# 03_-_28Pins_Schematic.net
KiCad netlist of a schematic drawn in Altium Designer
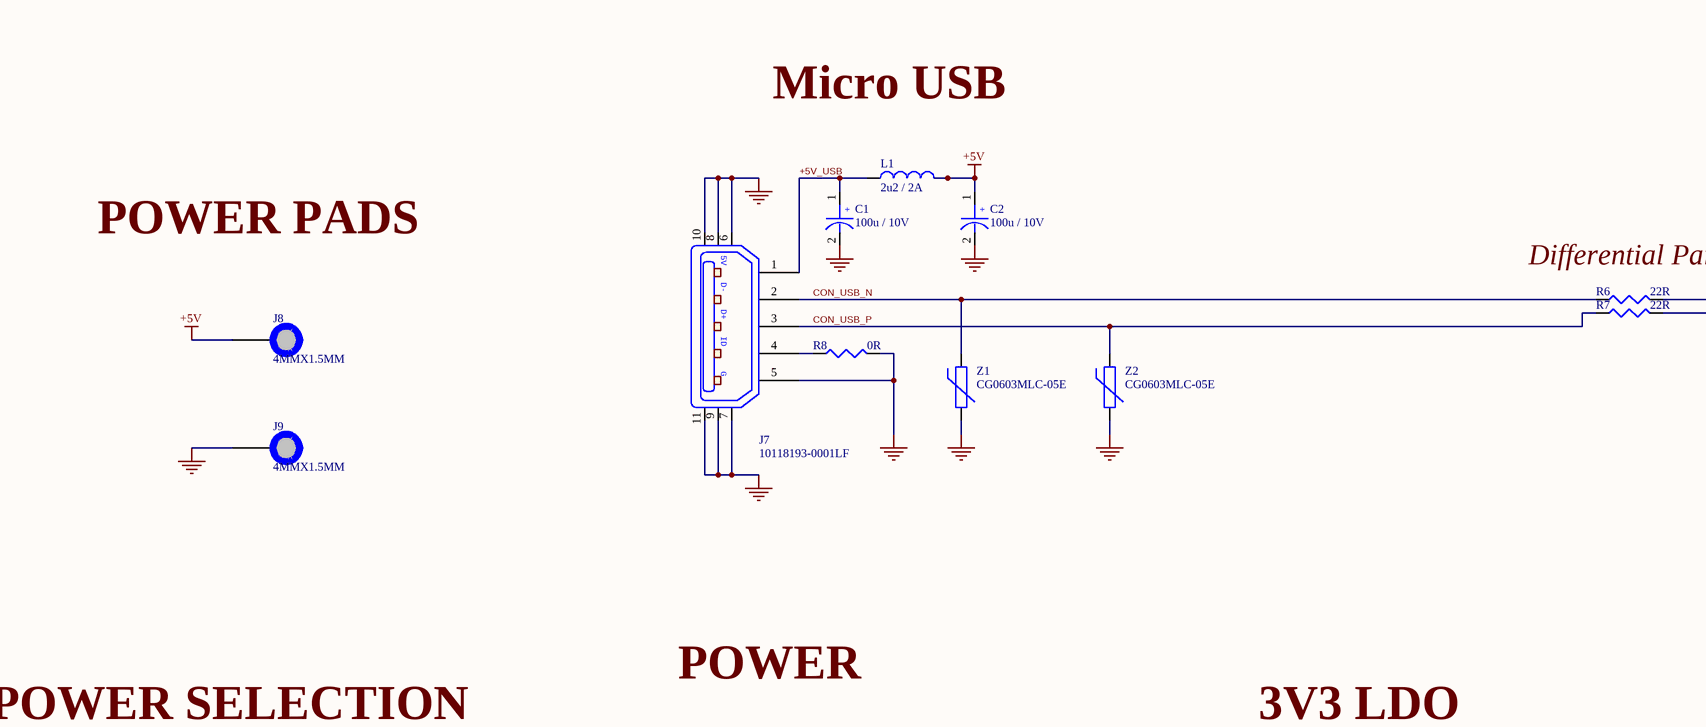
[diagram p0: [03] - 28Pins_Schematic.SchDoc, top left]
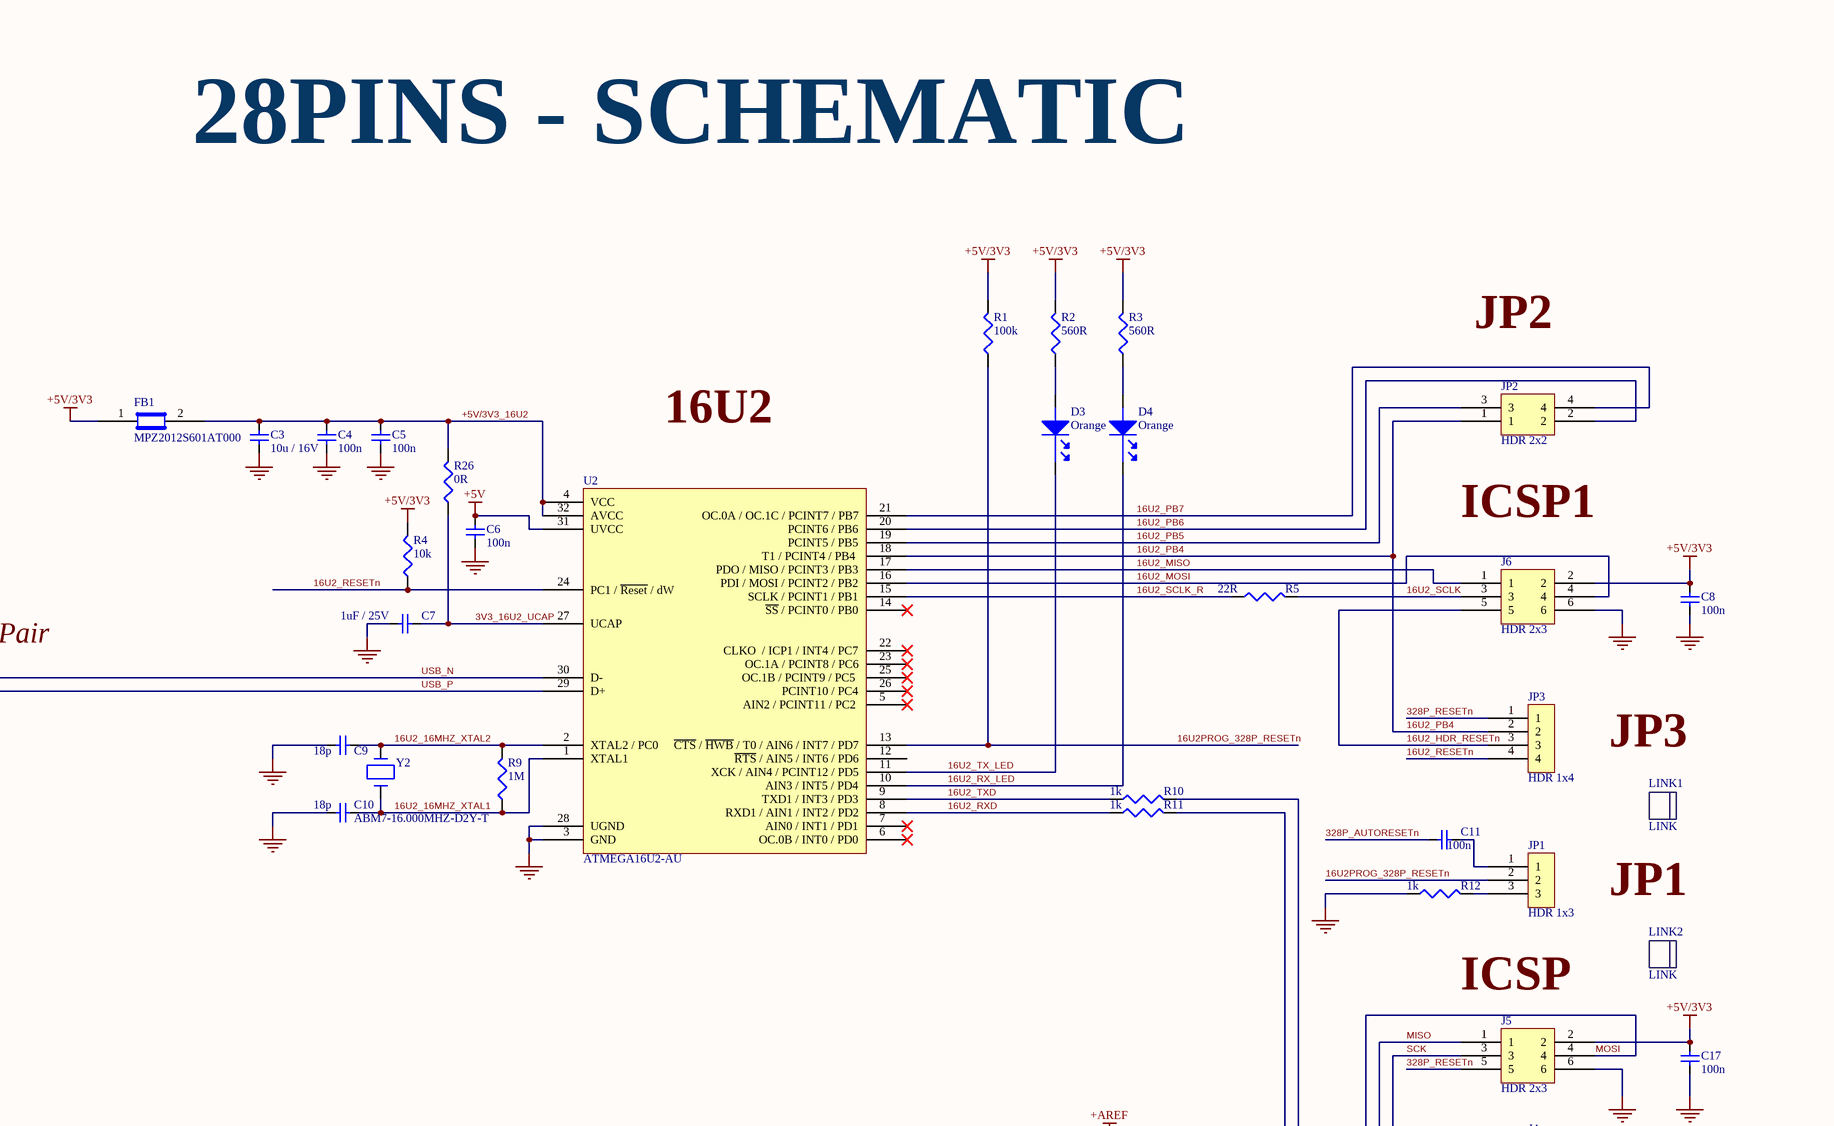
[diagram p1: [03] - 28Pins_Schematic.SchDoc, top middle]
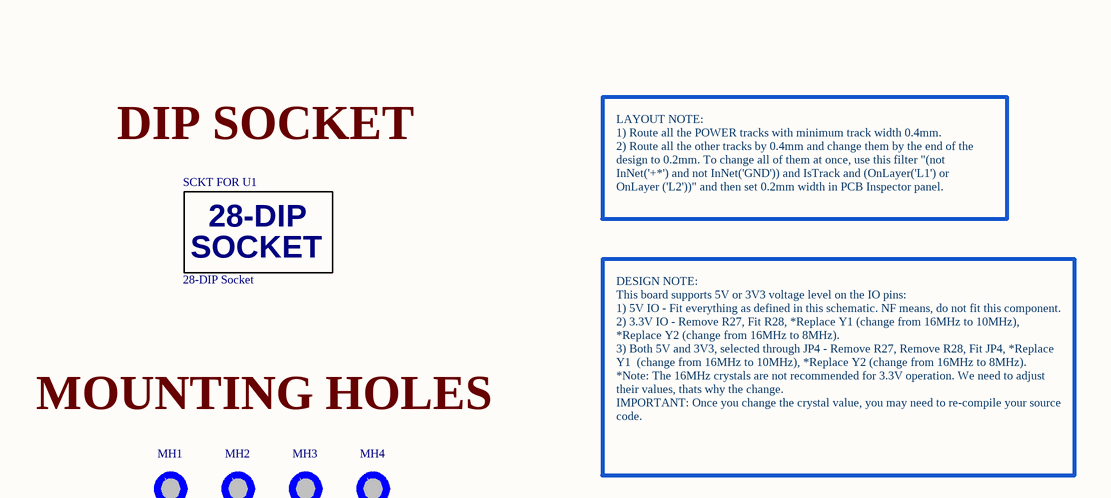
[diagram p2: [03] - 28Pins_Schematic.SchDoc, top right]
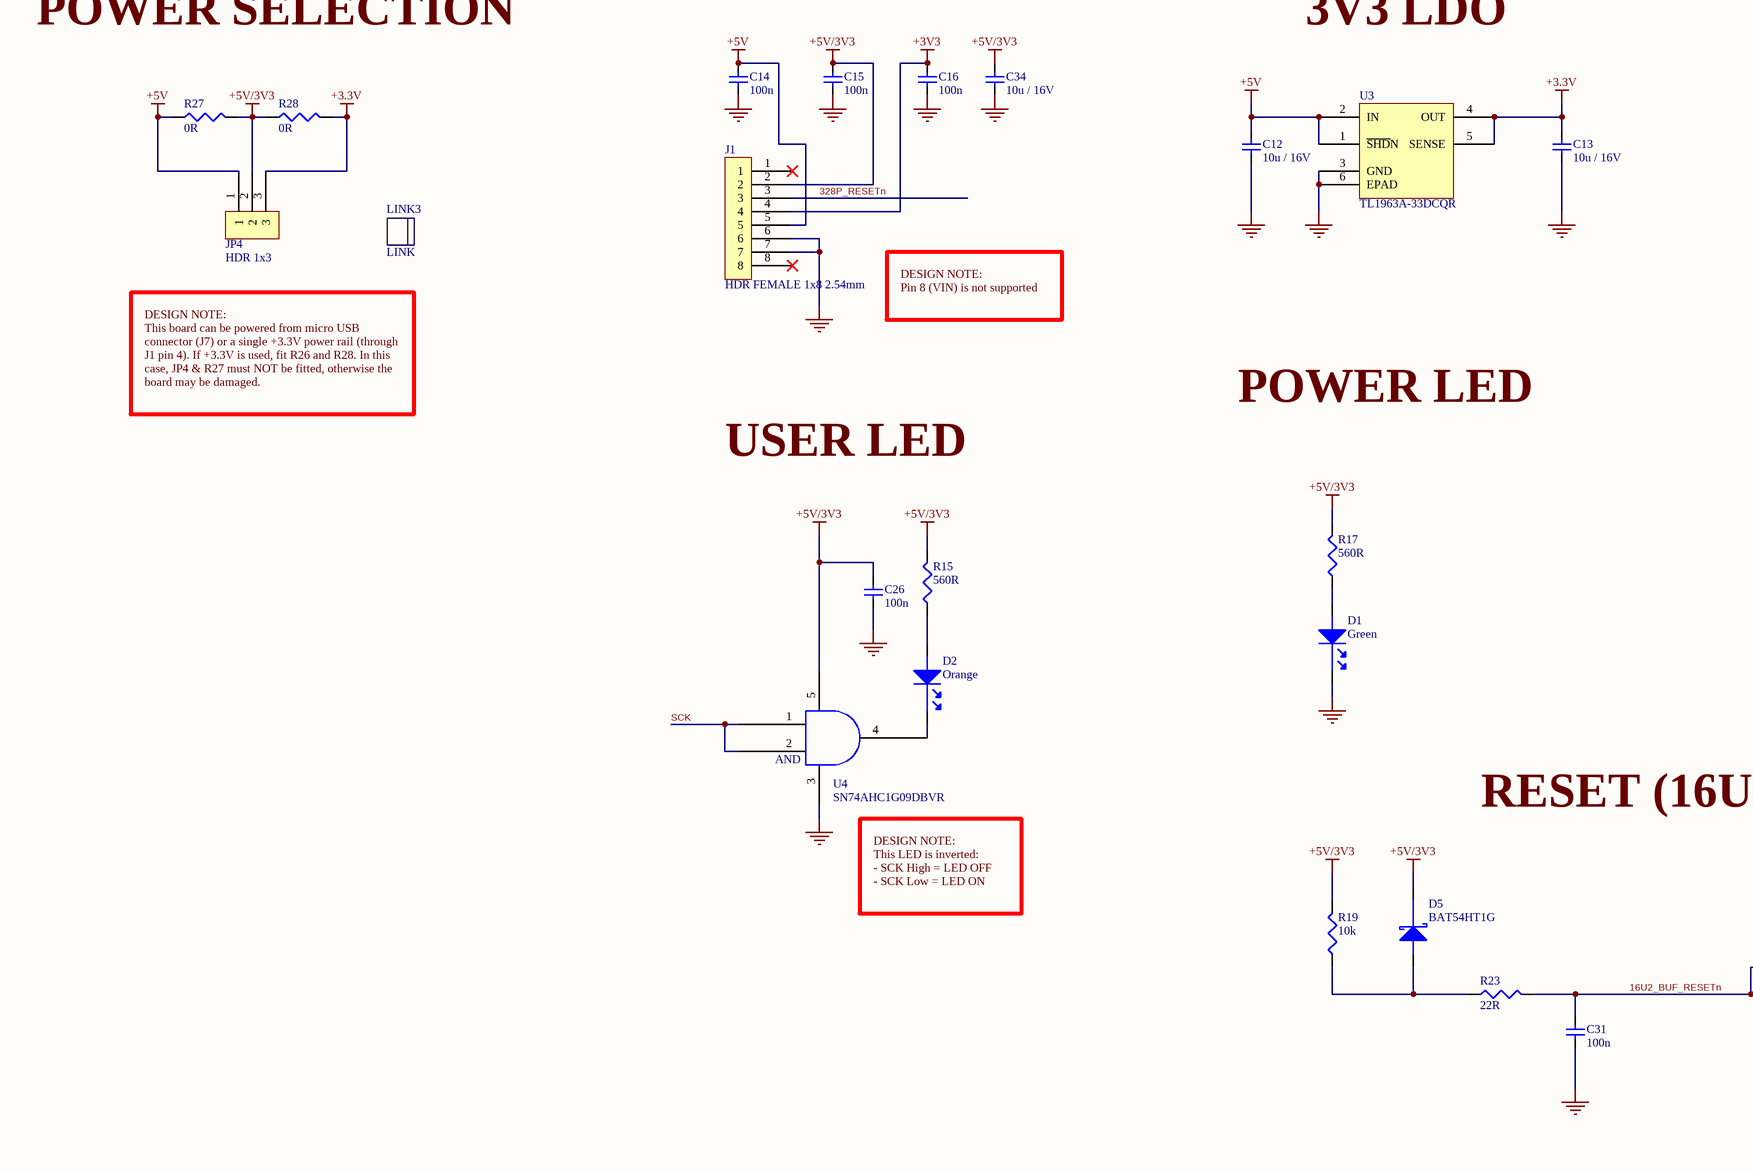
[diagram p3: [03] - 28Pins_Schematic.SchDoc, bottom left]
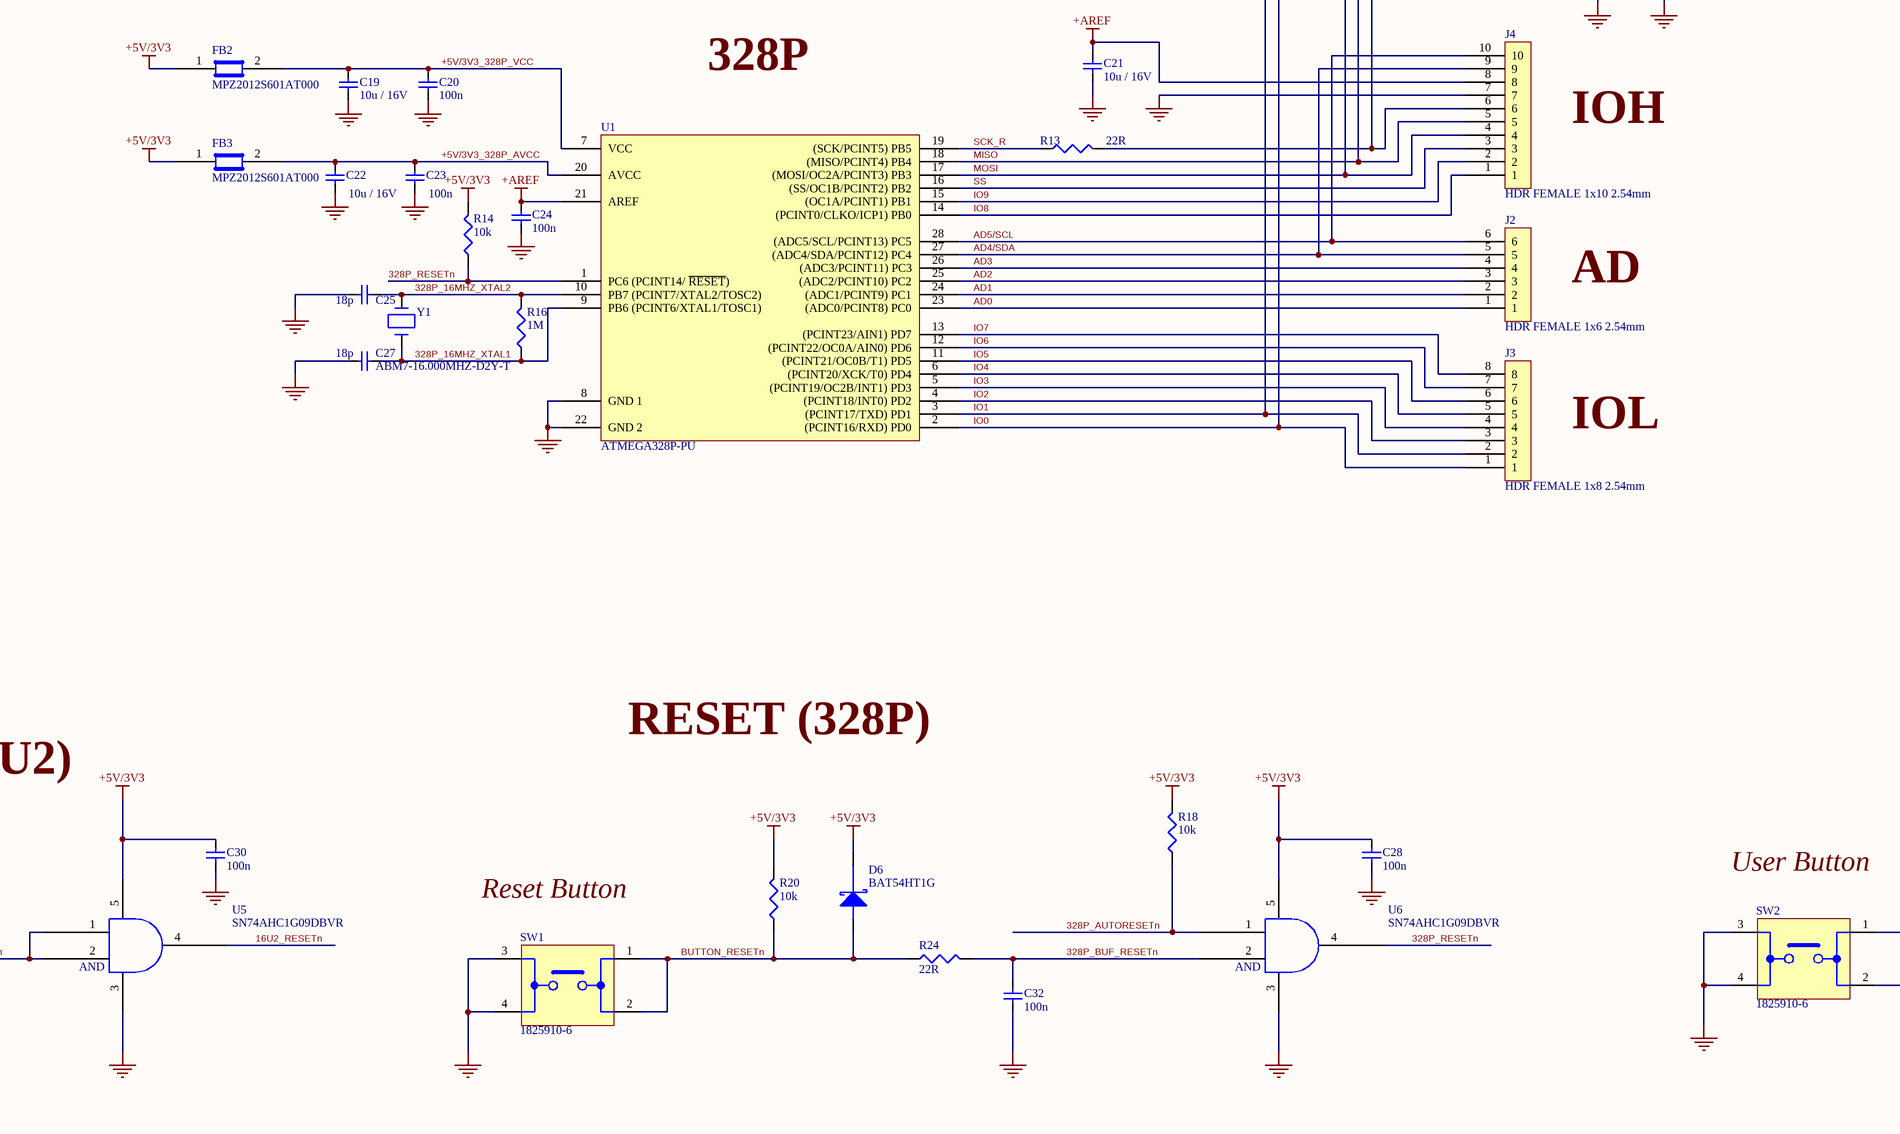
[diagram p4: [03] - 28Pins_Schematic.SchDoc, bottom middle]
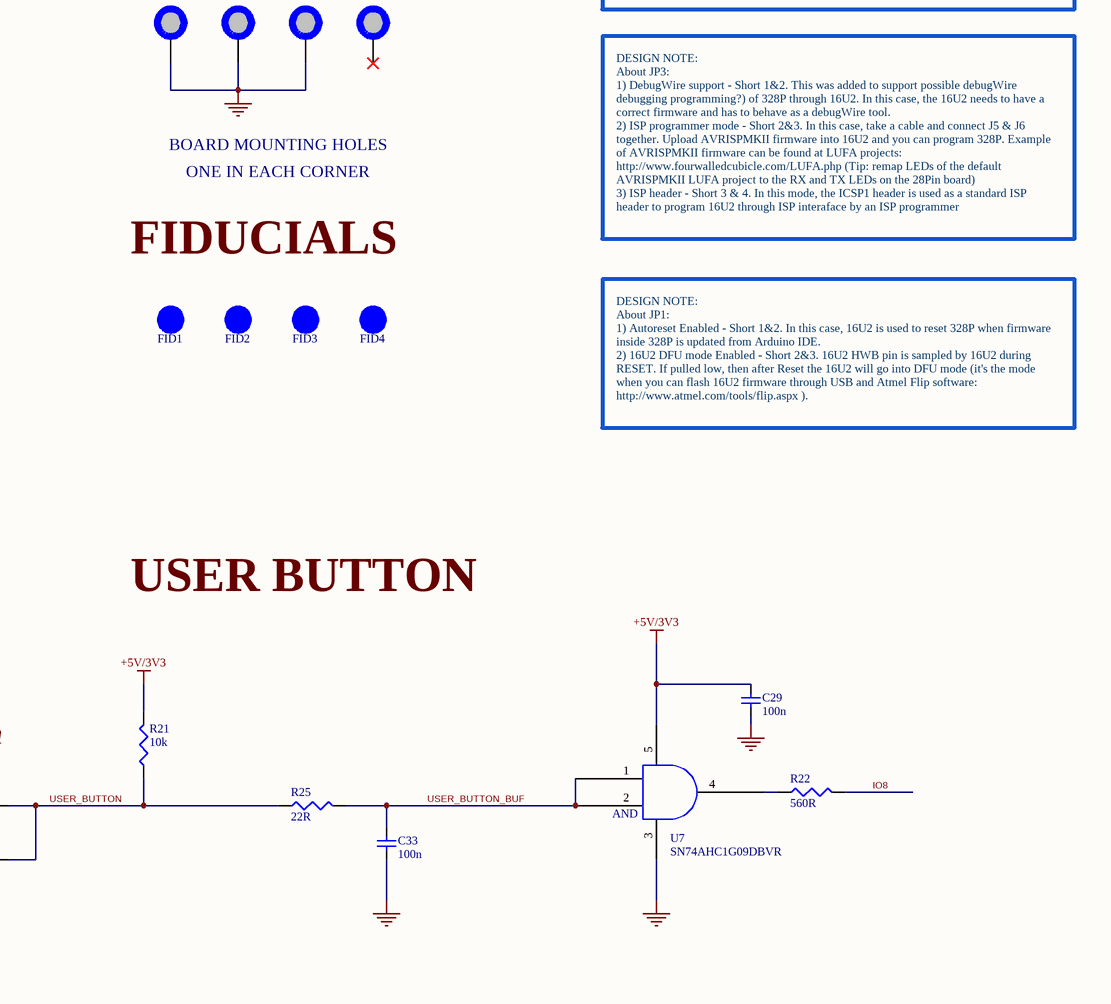
[diagram p5: [03] - 28Pins_Schematic.SchDoc, bottom right]

(export (version "E")
  (design (tool "Eeschema 10.0.6"))
  (components
    (comp (ref "C1")
      (value "100u / 10V")
      (footprint "C_ALU_C_SIZE")
      (description "Cap Aluminum 100uF 10V 20% (5 X 5.4mm) SMD 50mA 1000 hr 85°C T/R")
      (fields
        (field (name "MANUFACTURER") "Panasonic")
        (field (name "MANUFACTURER PART NUMBER") "EEE-1AA101WR")
      )
      (libsource (lib "28Pins") (part "EEE-1AA101WR"))
    )
    (comp (ref "C2")
      (value "100u / 10V")
      (footprint "C_ALU_C_SIZE")
      (description "Cap Aluminum 100uF 10V 20% (5 X 5.4mm) SMD 50mA 1000 hr 85°C T/R")
      (fields
        (field (name "MANUFACTURER") "Panasonic")
        (field (name "MANUFACTURER PART NUMBER") "EEE-1AA101WR")
      )
      (libsource (lib "28Pins") (part "EEE-1AA101WR"))
    )
    (comp (ref "C3")
      (value "10u / 16V")
      (footprint "C0805")
      (fields
        (field (name "MANUFACTURER") "TDK")
        (field (name "MANUFACTURER PART NUMBER") "C2012X5R1C106K085AC")
        (field (name "TOLERANCE") "10%")
      )
      (libsource (lib "28Pins") (part "C2012X5R1C106K085AC"))
    )
    (comp (ref "C4")
      (value "100n")
      (footprint "C0805")
      (fields
        (field (name "MANUFACTURER") "TDK")
        (field (name "MANUFACTURER PART NUMBER") "C2012X7R1H104K085AA")
        (field (name "TOLERANCE") "10%")
      )
      (libsource (lib "28Pins") (part "C2012X7R1H104K085AA"))
    )
    (comp (ref "C5")
      (value "100n")
      (footprint "C0805")
      (fields
        (field (name "MANUFACTURER") "TDK")
        (field (name "MANUFACTURER PART NUMBER") "C2012X7R1H104K085AA")
        (field (name "TOLERANCE") "10%")
      )
      (libsource (lib "28Pins") (part "C2012X7R1H104K085AA"))
    )
    (comp (ref "C6")
      (value "100n")
      (footprint "C0805")
      (fields
        (field (name "MANUFACTURER") "TDK")
        (field (name "MANUFACTURER PART NUMBER") "C2012X7R1H104K085AA")
        (field (name "TOLERANCE") "10%")
      )
      (libsource (lib "28Pins") (part "C2012X7R1H104K085AA"))
    )
    (comp (ref "C7")
      (value "1uF / 25V")
      (footprint "C0805")
      (fields
        (field (name "MANUFACTURER") "TDK")
        (field (name "MANUFACTURER PART NUMBER") "C2012X5R1E105K125AA")
        (field (name "TOLERANCE") "10%")
      )
      (libsource (lib "28Pins") (part "C2012X5R1E105K125AA"))
    )
    (comp (ref "C8")
      (value "100n")
      (footprint "C0805")
      (fields
        (field (name "MANUFACTURER") "TDK")
        (field (name "MANUFACTURER PART NUMBER") "C2012X7R1H104K085AA")
        (field (name "TOLERANCE") "10%")
      )
      (libsource (lib "28Pins") (part "C2012X7R1H104K085AA"))
    )
    (comp (ref "C9")
      (value "18p")
      (footprint "C0805")
      (description "CAP CER 18PF 50V C0G/NP0 0805")
      (fields
        (field (name "MANUFACTURER") "KEMET")
        (field (name "MANUFACTURER PART NUMBER") "C0805C180J5GACTU")
      )
      (libsource (lib "28Pins") (part "C0805C180J5GACTU"))
    )
    (comp (ref "C10")
      (value "18p")
      (footprint "C0805")
      (description "CAP CER 18PF 50V C0G/NP0 0805")
      (fields
        (field (name "MANUFACTURER") "KEMET")
        (field (name "MANUFACTURER PART NUMBER") "C0805C180J5GACTU")
      )
      (libsource (lib "28Pins") (part "C0805C180J5GACTU"))
    )
    (comp (ref "C11")
      (value "100n")
      (footprint "C0805")
      (fields
        (field (name "MANUFACTURER") "TDK")
        (field (name "MANUFACTURER PART NUMBER") "C2012X7R1H104K085AA")
        (field (name "TOLERANCE") "10%")
      )
      (libsource (lib "28Pins") (part "C2012X7R1H104K085AA"))
    )
    (comp (ref "C12")
      (value "10u / 16V")
      (footprint "C0805")
      (fields
        (field (name "MANUFACTURER") "TDK")
        (field (name "MANUFACTURER PART NUMBER") "C2012X5R1C106K085AC")
        (field (name "TOLERANCE") "10%")
      )
      (libsource (lib "28Pins") (part "C2012X5R1C106K085AC"))
    )
    (comp (ref "C13")
      (value "10u / 16V")
      (footprint "C0805")
      (fields
        (field (name "MANUFACTURER") "TDK")
        (field (name "MANUFACTURER PART NUMBER") "C2012X5R1C106K085AC")
        (field (name "TOLERANCE") "10%")
      )
      (libsource (lib "28Pins") (part "C2012X5R1C106K085AC"))
    )
    (comp (ref "C14")
      (value "100n")
      (footprint "C0805")
      (fields
        (field (name "MANUFACTURER") "TDK")
        (field (name "MANUFACTURER PART NUMBER") "C2012X7R1H104K085AA")
        (field (name "TOLERANCE") "10%")
      )
      (libsource (lib "28Pins") (part "C2012X7R1H104K085AA"))
    )
    (comp (ref "C15")
      (value "100n")
      (footprint "C0805")
      (fields
        (field (name "MANUFACTURER") "TDK")
        (field (name "MANUFACTURER PART NUMBER") "C2012X7R1H104K085AA")
        (field (name "TOLERANCE") "10%")
      )
      (libsource (lib "28Pins") (part "C2012X7R1H104K085AA"))
    )
    (comp (ref "C16")
      (value "100n")
      (footprint "C0805")
      (fields
        (field (name "MANUFACTURER") "TDK")
        (field (name "MANUFACTURER PART NUMBER") "C2012X7R1H104K085AA")
        (field (name "TOLERANCE") "10%")
      )
      (libsource (lib "28Pins") (part "C2012X7R1H104K085AA"))
    )
    (comp (ref "C17")
      (value "100n")
      (footprint "C0805")
      (fields
        (field (name "MANUFACTURER") "TDK")
        (field (name "MANUFACTURER PART NUMBER") "C2012X7R1H104K085AA")
        (field (name "TOLERANCE") "10%")
      )
      (libsource (lib "28Pins") (part "C2012X7R1H104K085AA"))
    )
    (comp (ref "C19")
      (value "10u / 16V")
      (footprint "C0805")
      (fields
        (field (name "MANUFACTURER") "TDK")
        (field (name "MANUFACTURER PART NUMBER") "C2012X5R1C106K085AC")
        (field (name "TOLERANCE") "10%")
      )
      (libsource (lib "28Pins") (part "C2012X5R1C106K085AC"))
    )
    (comp (ref "C20")
      (value "100n")
      (footprint "C0805")
      (fields
        (field (name "MANUFACTURER") "TDK")
        (field (name "MANUFACTURER PART NUMBER") "C2012X7R1H104K085AA")
        (field (name "TOLERANCE") "10%")
      )
      (libsource (lib "28Pins") (part "C2012X7R1H104K085AA"))
    )
    (comp (ref "C21")
      (value "10u / 16V")
      (footprint "C0805")
      (fields
        (field (name "MANUFACTURER") "TDK")
        (field (name "MANUFACTURER PART NUMBER") "C2012X5R1C106K085AC")
        (field (name "TOLERANCE") "10%")
      )
      (libsource (lib "28Pins") (part "C2012X5R1C106K085AC"))
    )
    (comp (ref "C22")
      (value "10u / 16V")
      (footprint "C0805")
      (fields
        (field (name "MANUFACTURER") "TDK")
        (field (name "MANUFACTURER PART NUMBER") "C2012X5R1C106K085AC")
        (field (name "TOLERANCE") "10%")
      )
      (libsource (lib "28Pins") (part "C2012X5R1C106K085AC"))
    )
    (comp (ref "C23")
      (value "100n")
      (footprint "C0805")
      (fields
        (field (name "MANUFACTURER") "TDK")
        (field (name "MANUFACTURER PART NUMBER") "C2012X7R1H104K085AA")
        (field (name "TOLERANCE") "10%")
      )
      (libsource (lib "28Pins") (part "C2012X7R1H104K085AA"))
    )
    (comp (ref "C24")
      (value "100n")
      (footprint "C0805")
      (fields
        (field (name "MANUFACTURER") "TDK")
        (field (name "MANUFACTURER PART NUMBER") "C2012X7R1H104K085AA")
        (field (name "TOLERANCE") "10%")
      )
      (libsource (lib "28Pins") (part "C2012X7R1H104K085AA"))
    )
    (comp (ref "C25")
      (value "18p")
      (footprint "C0805")
      (description "CAP CER 18PF 50V C0G/NP0 0805")
      (fields
        (field (name "MANUFACTURER") "KEMET")
        (field (name "MANUFACTURER PART NUMBER") "C0805C180J5GACTU")
      )
      (libsource (lib "28Pins") (part "C0805C180J5GACTU"))
    )
    (comp (ref "C26")
      (value "100n")
      (footprint "C0805")
      (fields
        (field (name "MANUFACTURER") "TDK")
        (field (name "MANUFACTURER PART NUMBER") "C2012X7R1H104K085AA")
        (field (name "TOLERANCE") "10%")
      )
      (libsource (lib "28Pins") (part "C2012X7R1H104K085AA"))
    )
    (comp (ref "C27")
      (value "18p")
      (footprint "C0805")
      (description "CAP CER 18PF 50V C0G/NP0 0805")
      (fields
        (field (name "MANUFACTURER") "KEMET")
        (field (name "MANUFACTURER PART NUMBER") "C0805C180J5GACTU")
      )
      (libsource (lib "28Pins") (part "C0805C180J5GACTU"))
    )
    (comp (ref "C28")
      (value "100n")
      (footprint "C0805")
      (fields
        (field (name "MANUFACTURER") "TDK")
        (field (name "MANUFACTURER PART NUMBER") "C2012X7R1H104K085AA")
        (field (name "TOLERANCE") "10%")
      )
      (libsource (lib "28Pins") (part "C2012X7R1H104K085AA"))
    )
    (comp (ref "C29")
      (value "100n")
      (footprint "C0805")
      (fields
        (field (name "MANUFACTURER") "TDK")
        (field (name "MANUFACTURER PART NUMBER") "C2012X7R1H104K085AA")
        (field (name "TOLERANCE") "10%")
      )
      (libsource (lib "28Pins") (part "C2012X7R1H104K085AA"))
    )
    (comp (ref "C30")
      (value "100n")
      (footprint "C0805")
      (fields
        (field (name "MANUFACTURER") "TDK")
        (field (name "MANUFACTURER PART NUMBER") "C2012X7R1H104K085AA")
        (field (name "TOLERANCE") "10%")
      )
      (libsource (lib "28Pins") (part "C2012X7R1H104K085AA"))
    )
    (comp (ref "C31")
      (value "100n")
      (footprint "C0805")
      (fields
        (field (name "MANUFACTURER") "TDK")
        (field (name "MANUFACTURER PART NUMBER") "C2012X7R1H104K085AA")
        (field (name "TOLERANCE") "10%")
      )
      (libsource (lib "28Pins") (part "C2012X7R1H104K085AA"))
    )
    (comp (ref "C32")
      (value "100n")
      (footprint "C0805")
      (fields
        (field (name "MANUFACTURER") "TDK")
        (field (name "MANUFACTURER PART NUMBER") "C2012X7R1H104K085AA")
        (field (name "TOLERANCE") "10%")
      )
      (libsource (lib "28Pins") (part "C2012X7R1H104K085AA"))
    )
    (comp (ref "C33")
      (value "100n")
      (footprint "C0805")
      (fields
        (field (name "MANUFACTURER") "TDK")
        (field (name "MANUFACTURER PART NUMBER") "C2012X7R1H104K085AA")
        (field (name "TOLERANCE") "10%")
      )
      (libsource (lib "28Pins") (part "C2012X7R1H104K085AA"))
    )
    (comp (ref "C34")
      (value "10u / 16V")
      (footprint "C0805")
      (fields
        (field (name "MANUFACTURER") "TDK")
        (field (name "MANUFACTURER PART NUMBER") "C2012X5R1C106K085AC")
        (field (name "TOLERANCE") "10%")
      )
      (libsource (lib "28Pins") (part "C2012X5R1C106K085AC"))
    )
    (comp (ref "D1")
      (value "Green")
      (footprint "LED_0603")
      (description "LED Uni-Color Green 572nm Automotive 2-Pin Chip 0603(1608Metric) T/R")
      (fields
        (field (name "MANUFACTURER") "Osram Opto")
        (field (name "MANUFACTURER PART NUMBER") "LGL29K-F2J1-24-Z")
      )
      (libsource (lib "28Pins") (part "LGL29K-F2J1-24-Z"))
    )
    (comp (ref "D2")
      (value "Orange")
      (footprint "LED_0603")
      (description "LED Uni-Color Orange 610nm 2-Pin Case 0603 T/R")
      (fields
        (field (name "MANUFACTURER") "Osram Opto")
        (field (name "MANUFACTURER PART NUMBER") "LOL29K-H2K1-24")
      )
      (libsource (lib "28Pins") (part "LOL29K-H2K1-24"))
    )
    (comp (ref "D3")
      (value "Orange")
      (footprint "LED_0603")
      (description "LED Uni-Color Orange 610nm 2-Pin Case 0603 T/R")
      (fields
        (field (name "MANUFACTURER") "Osram Opto")
        (field (name "MANUFACTURER PART NUMBER") "LOL29K-H2K1-24")
      )
      (libsource (lib "28Pins") (part "LOL29K-H2K1-24"))
    )
    (comp (ref "D4")
      (value "Orange")
      (footprint "LED_0603")
      (description "LED Uni-Color Orange 610nm 2-Pin Case 0603 T/R")
      (fields
        (field (name "MANUFACTURER") "Osram Opto")
        (field (name "MANUFACTURER PART NUMBER") "LOL29K-H2K1-24")
      )
      (libsource (lib "28Pins") (part "LOL29K-H2K1-24"))
    )
    (comp (ref "D5")
      (value "BAT54HT1G")
      (footprint "SOD323")
      (description "Small Signal Schottky Diode, Single, 30 V, 200 mA, 800 mV, 600 mA, 150 C ;RoHS Compliant: Yes")
      (fields (field (name "MANUFACTURER") "ON Semiconductor / Fairchild"))
      (libsource (lib "28Pins") (part "BAT54HT1G"))
    )
    (comp (ref "D6")
      (value "BAT54HT1G")
      (footprint "SOD323")
      (description "Small Signal Schottky Diode, Single, 30 V, 200 mA, 800 mV, 600 mA, 150 C ;RoHS Compliant: Yes")
      (fields (field (name "MANUFACTURER") "ON Semiconductor / Fairchild"))
      (libsource (lib "28Pins") (part "BAT54HT1G"))
    )
    (comp (ref "FB1")
      (value "MPZ2012S601AT000")
      (footprint "C0805")
      (description "FERRITE BEAD 600 OHM 0805 1LN")
      (fields (field (name "MANUFACTURER") "TDK"))
      (libsource (lib "28Pins") (part "MPZ2012S601AT000"))
    )
    (comp (ref "FB2")
      (value "MPZ2012S601AT000")
      (footprint "C0805")
      (description "FERRITE BEAD 600 OHM 0805 1LN")
      (fields (field (name "MANUFACTURER") "TDK"))
      (libsource (lib "28Pins") (part "MPZ2012S601AT000"))
    )
    (comp (ref "FB3")
      (value "MPZ2012S601AT000")
      (footprint "C0805")
      (description "FERRITE BEAD 600 OHM 0805 1LN")
      (fields (field (name "MANUFACTURER") "TDK"))
      (libsource (lib "28Pins") (part "MPZ2012S601AT000"))
    )
    (comp (ref "FID1")
      (value "FID_1MMC")
      (footprint "FID_40X120D")
      (description "Fiducial 40mil Diameter, 120mil Mask")
      (libsource (lib "28Pins") (part "FID_1MMC"))
    )
    (comp (ref "FID2")
      (value "FID_1MMC")
      (footprint "FID_40X120D")
      (description "Fiducial 40mil Diameter, 120mil Mask")
      (libsource (lib "28Pins") (part "FID_1MMC"))
    )
    (comp (ref "FID3")
      (value "FID_1MMC")
      (footprint "FID_40X120D")
      (description "Fiducial 40mil Diameter, 120mil Mask")
      (libsource (lib "28Pins") (part "FID_1MMC"))
    )
    (comp (ref "FID4")
      (value "FID_1MMC")
      (footprint "FID_40X120D")
      (description "Fiducial 40mil Diameter, 120mil Mask")
      (libsource (lib "28Pins") (part "FID_1MMC"))
    )
    (comp (ref "J1")
      (value "HDR FEMALE 1x8 2.54mm")
      (footprint "Hdr_Female_1x8_2.54mm")
      (description "2.54mm (0.1\") Pitch SIL Vertical PC Tail Socket Assembly, selective gold + tin, 8 contacts")
      (fields (field (name "MANUFACTURER") "Harwin") (field (name "MANUFACTURER PART NUMBER") "M20-7820842"))
      (libsource (lib "") (part "M20-7820842_1"))
    )
    (comp (ref "J2")
      (value "HDR FEMALE 1x6 2.54mm")
      (footprint "Hdr_Female_1x6_2.54mm")
      (description "06-WAY SIL VERT SOCKET L/FREE")
      (fields (field (name "MANUFACTURER") "Harwin") (field (name "MANUFACTURER PART NUMBER") "M20-7820646"))
      (libsource (lib "28Pins") (part "M20-7820646"))
    )
    (comp (ref "J3")
      (value "HDR FEMALE 1x8 2.54mm")
      (footprint "Hdr_Female_1x8_2.54mm")
      (description "2.54mm (0.1\") Pitch SIL Vertical PC Tail Socket Assembly, selective gold + tin, 8 contacts")
      (fields (field (name "MANUFACTURER") "Harwin") (field (name "MANUFACTURER PART NUMBER") "M20-7820842"))
      (libsource (lib "28Pins") (part "M20-7820842"))
    )
    (comp (ref "J4")
      (value "HDR FEMALE 1x10 2.54mm")
      (footprint "Hdr_Female_1x10_2.54mm")
      (fields (field (name "MANUFACTURER") "Harwin") (field (name "MANUFACTURER PART NUMBER") "M20-7821046"))
      (libsource (lib "28Pins") (part "M20-7821046"))
    )
    (comp (ref "J5")
      (value "HDR 2x3")
      (footprint "HDR_2x3_2.54MM")
      (description "CONN HEADER 6POS .100 STR 30AU")
      (fields
        (field (name "MANUFACTURER") "Amphenol FCI")
        (field (name "MANUFACTURER PART NUMBER") "67997-106HLF")
      )
      (libsource (lib "28Pins") (part "67997-106HLF"))
    )
    (comp (ref "J6")
      (value "HDR 2x3")
      (footprint "HDR_2x3_2.54MM")
      (description "CONN HEADER 6POS .100 STR 30AU")
      (fields
        (field (name "MANUFACTURER") "Amphenol FCI")
        (field (name "MANUFACTURER PART NUMBER") "67997-106HLF")
      )
      (libsource (lib "28Pins") (part "67997-106HLF"))
    )
    (comp (ref "J7")
      (value "10118193-0001LF")
      (footprint "10118193")
      (description "CONN USB MICRO B RECPT SMT R/A")
      (fields (field (name "MANUFACTURER") "Amphenol FCI"))
      (libsource (lib "28Pins") (part "10118193-0001LF"))
    )
    (comp (ref "J8")
      (value "4MMX1.5MM")
      (footprint "PAD_WITH_HOLE_4MMX1.5MM")
      (description "Pad with a hole 4mm x 1.5mm")
      (libsource (lib "28Pins") (part "PAD_WITH_HOLE_4MMX1.5MM"))
    )
    (comp (ref "J9")
      (value "4MMX1.5MM")
      (footprint "PAD_WITH_HOLE_4MMX1.5MM")
      (description "Pad with a hole 4mm x 1.5mm")
      (libsource (lib "28Pins") (part "PAD_WITH_HOLE_4MMX1.5MM"))
    )
    (comp (ref "JP1")
      (value "HDR 1x3")
      (footprint "Hdr_1x3_2.54mm")
      (description "Conn Unshrouded Header HDR 3 POS 2.54mm Solder ST Thru-Hole Bulk")
      (fields
        (field (name "MANUFACTURER") "Amphenol FCI")
        (field (name "MANUFACTURER PART NUMBER") "68000-103HLF")
      )
      (libsource (lib "") (part "68000-103HLF_1"))
    )
    (comp (ref "JP2")
      (value "HDR 2x2")
      (footprint "HDR_2x2_2.54MM")
      (description "CONN HEADER VERT 4POS 2.54MM")
      (fields
        (field (name "MANUFACTURER") "Amphenol FCI")
        (field (name "MANUFACTURER PART NUMBER") "68602-204HLF")
      )
      (libsource (lib "28Pins") (part "68602-204HLF"))
    )
    (comp (ref "JP3")
      (value "HDR 1x4")
      (footprint "Hdr_1x4_2.54MM")
      (description "CONN HEADER VERT 4POS 2.54MM")
      (fields
        (field (name "MANUFACTURER") "Amphenol FCI")
        (field (name "MANUFACTURER PART NUMBER") "68001-204HLF")
      )
      (libsource (lib "28Pins") (part "68001-204HLF"))
    )
    (comp (ref "JP4")
      (value "HDR 1x3")
      (footprint "Hdr_1x3_2.54mm")
      (description "Conn Unshrouded Header HDR 3 POS 2.54mm Solder ST Thru-Hole Bulk")
      (fields
        (field (name "MANUFACTURER") "Amphenol FCI")
        (field (name "MANUFACTURER PART NUMBER") "68000-103HLF")
      )
      (libsource (lib "28Pins") (part "68000-103HLF"))
    )
    (comp (ref "L1")
      (value "2u2 / 2A")
      (footprint "C1210_IND")
      (description "FIXED IND 2.2UH 2A 80 MOHM SMD")
      (fields
        (field (name "MANUFACTURER") "KEMET")
        (field (name "MANUFACTURER PART NUMBER") "L1210R2R2MDWIT")
      )
      (libsource (lib "28Pins") (part "L1210R2R2MDWIT"))
    )
    (comp (ref "LINK1")
      (value "LINK")
      (description "CONN JUMPER SHORTING .100\" GOLD")
      (fields
        (field (name "MANUFACTURER") "Sullins")
        (field (name "MANUFACTURER PART NUMBER") "QPC02SXGN-RC")
      )
      (libsource (lib "28Pins") (part "QPC02SXGN-RC"))
    )
    (comp (ref "LINK2")
      (value "LINK")
      (description "CONN JUMPER SHORTING .100\" GOLD")
      (fields
        (field (name "MANUFACTURER") "Sullins")
        (field (name "MANUFACTURER PART NUMBER") "QPC02SXGN-RC")
      )
      (libsource (lib "28Pins") (part "QPC02SXGN-RC"))
    )
    (comp (ref "LINK3")
      (value "LINK")
      (description "CONN JUMPER SHORTING .100\" GOLD")
      (fields
        (field (name "MANUFACTURER") "Sullins")
        (field (name "MANUFACTURER PART NUMBER") "QPC02SXGN-RC")
      )
      (libsource (lib "28Pins") (part "QPC02SXGN-RC"))
    )
    (comp (ref "MH1")
      (value "MH_7.4MMC_3.2MMD")
      (footprint "MH_7.4MMC_3.2MMD")
      (description "Mounting Hole 7.4mm Diameter, 3.2 Drill")
      (libsource (lib "28Pins") (part "MH_7.4MMC_3.2MMD"))
    )
    (comp (ref "MH2")
      (value "MH_7.4MMC_3.2MMD")
      (footprint "MH_7.4MMC_3.2MMD")
      (description "Mounting Hole 7.4mm Diameter, 3.2 Drill")
      (libsource (lib "28Pins") (part "MH_7.4MMC_3.2MMD"))
    )
    (comp (ref "MH3")
      (value "MH_7.4MMC_3.2MMD")
      (footprint "MH_7.4MMC_3.2MMD")
      (description "Mounting Hole 7.4mm Diameter, 3.2 Drill")
      (libsource (lib "28Pins") (part "MH_7.4MMC_3.2MMD"))
    )
    (comp (ref "MH4")
      (value "MH_7.4MMNC_3.2MMD")
      (footprint "MH_7.4MMC_3.2MMD_NON_COPPER_NPTH")
      (description "Hole 7.4mm Diameter (Non Copper), 3.2 Drill NPTH.")
      (libsource (lib "28Pins") (part "MH_7.4MMNC_3.2MMD"))
    )
    (comp (ref "R1")
      (value "100k")
      (footprint "R0805")
      (description "YAGEO         RC0805FR-07100KL            RES, THICK FILM, 100K, 1%, 0.125W, 0805, REEL")
      (fields
        (field (name "MANUFACTURER") "Yageo")
        (field (name "MANUFACTURER PART NUMBER") "RC0805FR-07100KL")
      )
      (libsource (lib "28Pins") (part "RC0805FR-07100KL"))
    )
    (comp (ref "R2")
      (value "560R")
      (footprint "R0805")
      (description "Surface Mount Thick Film Resistor, RC Series, 560 ohm, 125 mW, - 1%, 150 V, 0805 [2012 Metric]")
      (fields
        (field (name "MANUFACTURER") "Yageo")
        (field (name "MANUFACTURER PART NUMBER") "RC0805FR-07560RL")
      )
      (libsource (lib "28Pins") (part "RC0805FR-07560RL"))
    )
    (comp (ref "R3")
      (value "560R")
      (footprint "R0805")
      (description "Surface Mount Thick Film Resistor, RC Series, 560 ohm, 125 mW, - 1%, 150 V, 0805 [2012 Metric]")
      (fields
        (field (name "MANUFACTURER") "Yageo")
        (field (name "MANUFACTURER PART NUMBER") "RC0805FR-07560RL")
      )
      (libsource (lib "28Pins") (part "RC0805FR-07560RL"))
    )
    (comp (ref "R4")
      (value "10k")
      (footprint "R0805")
      (description "RES SMD 10K OHM 1% 1/8W 0805")
      (fields
        (field (name "MANUFACTURER") "Yageo")
        (field (name "MANUFACTURER PART NUMBER") "RC0805FR-0710KL")
      )
      (libsource (lib "28Pins") (part "RC0805FR-0710KL"))
    )
    (comp (ref "R5")
      (value "22R")
      (footprint "R0805")
      (description "RES SMD 22 OHM 1% 1/8W 0805")
      (fields
        (field (name "MANUFACTURER") "Yageo")
        (field (name "MANUFACTURER PART NUMBER") "RC0805FR-0722RL")
      )
      (libsource (lib "28Pins") (part "RC0805FR-0722RL"))
    )
    (comp (ref "R6")
      (value "22R")
      (footprint "R0805")
      (description "RES SMD 22 OHM 1% 1/8W 0805")
      (fields
        (field (name "MANUFACTURER") "Yageo")
        (field (name "MANUFACTURER PART NUMBER") "RC0805FR-0722RL")
      )
      (libsource (lib "28Pins") (part "RC0805FR-0722RL"))
    )
    (comp (ref "R7")
      (value "22R")
      (footprint "R0805")
      (description "RES SMD 22 OHM 1% 1/8W 0805")
      (fields
        (field (name "MANUFACTURER") "Yageo")
        (field (name "MANUFACTURER PART NUMBER") "RC0805FR-0722RL")
      )
      (libsource (lib "28Pins") (part "RC0805FR-0722RL"))
    )
    (comp (ref "R8")
      (value "0R")
      (footprint "R0805")
      (description "Surface Mount Thick Film Resistor, RC Series, 125 mW, - 5%, 150 V, 0805 [2012 Metric]")
      (fields
        (field (name "MANUFACTURER") "Yageo")
        (field (name "MANUFACTURER PART NUMBER") "RC0805JR-070RL")
      )
      (libsource (lib "28Pins") (part "RC0805JR-070RL"))
    )
    (comp (ref "R9")
      (value "1M")
      (footprint "R0805")
      (description "RES SMD 1M OHM 1% 1/8W 0805")
      (fields
        (field (name "MANUFACTURER") "Yageo")
        (field (name "MANUFACTURER PART NUMBER") "RC0805FR-071ML")
      )
      (libsource (lib "28Pins") (part "RC0805FR-071ML"))
    )
    (comp (ref "R10")
      (value "1k")
      (footprint "R0805")
      (fields
        (field (name "MANUFACTURER") "Yageo")
        (field (name "MANUFACTURER PART NUMBER") "RC0805FR-071KL")
        (field (name "TOLERANCE") "1%")
      )
      (libsource (lib "28Pins") (part "RC0805FR-071KL"))
    )
    (comp (ref "R11")
      (value "1k")
      (footprint "R0805")
      (fields
        (field (name "MANUFACTURER") "Yageo")
        (field (name "MANUFACTURER PART NUMBER") "RC0805FR-071KL")
        (field (name "TOLERANCE") "1%")
      )
      (libsource (lib "28Pins") (part "RC0805FR-071KL"))
    )
    (comp (ref "R12")
      (value "1k")
      (footprint "R0805")
      (fields
        (field (name "MANUFACTURER") "Yageo")
        (field (name "MANUFACTURER PART NUMBER") "RC0805FR-071KL")
        (field (name "TOLERANCE") "1%")
      )
      (libsource (lib "28Pins") (part "RC0805FR-071KL"))
    )
    (comp (ref "R13")
      (value "22R")
      (footprint "R0805")
      (description "RES SMD 22 OHM 1% 1/8W 0805")
      (fields
        (field (name "MANUFACTURER") "Yageo")
        (field (name "MANUFACTURER PART NUMBER") "RC0805FR-0722RL")
      )
      (libsource (lib "28Pins") (part "RC0805FR-0722RL"))
    )
    (comp (ref "R14")
      (value "10k")
      (footprint "R0805")
      (description "RES SMD 10K OHM 1% 1/8W 0805")
      (fields
        (field (name "MANUFACTURER") "Yageo")
        (field (name "MANUFACTURER PART NUMBER") "RC0805FR-0710KL")
      )
      (libsource (lib "28Pins") (part "RC0805FR-0710KL"))
    )
    (comp (ref "R15")
      (value "560R")
      (footprint "R0805")
      (description "Surface Mount Thick Film Resistor, RC Series, 560 ohm, 125 mW, - 1%, 150 V, 0805 [2012 Metric]")
      (fields
        (field (name "MANUFACTURER") "Yageo")
        (field (name "MANUFACTURER PART NUMBER") "RC0805FR-07560RL")
      )
      (libsource (lib "28Pins") (part "RC0805FR-07560RL"))
    )
    (comp (ref "R16")
      (value "1M")
      (footprint "R0805")
      (description "RES SMD 1M OHM 1% 1/8W 0805")
      (fields
        (field (name "MANUFACTURER") "Yageo")
        (field (name "MANUFACTURER PART NUMBER") "RC0805FR-071ML")
      )
      (libsource (lib "28Pins") (part "RC0805FR-071ML"))
    )
    (comp (ref "R17")
      (value "560R")
      (footprint "R0805")
      (description "Surface Mount Thick Film Resistor, RC Series, 560 ohm, 125 mW, - 1%, 150 V, 0805 [2012 Metric]")
      (fields
        (field (name "MANUFACTURER") "Yageo")
        (field (name "MANUFACTURER PART NUMBER") "RC0805FR-07560RL")
      )
      (libsource (lib "28Pins") (part "RC0805FR-07560RL"))
    )
    (comp (ref "R18")
      (value "10k")
      (footprint "R0805")
      (description "RES SMD 10K OHM 1% 1/8W 0805")
      (fields
        (field (name "MANUFACTURER") "Yageo")
        (field (name "MANUFACTURER PART NUMBER") "RC0805FR-0710KL")
      )
      (libsource (lib "28Pins") (part "RC0805FR-0710KL"))
    )
    (comp (ref "R19")
      (value "10k")
      (footprint "R0805")
      (description "RES SMD 10K OHM 1% 1/8W 0805")
      (fields
        (field (name "MANUFACTURER") "Yageo")
        (field (name "MANUFACTURER PART NUMBER") "RC0805FR-0710KL")
      )
      (libsource (lib "28Pins") (part "RC0805FR-0710KL"))
    )
    (comp (ref "R20")
      (value "10k")
      (footprint "R0805")
      (description "RES SMD 10K OHM 1% 1/8W 0805")
      (fields
        (field (name "MANUFACTURER") "Yageo")
        (field (name "MANUFACTURER PART NUMBER") "RC0805FR-0710KL")
      )
      (libsource (lib "28Pins") (part "RC0805FR-0710KL"))
    )
    (comp (ref "R21")
      (value "10k")
      (footprint "R0805")
      (description "RES SMD 10K OHM 1% 1/8W 0805")
      (fields
        (field (name "MANUFACTURER") "Yageo")
        (field (name "MANUFACTURER PART NUMBER") "RC0805FR-0710KL")
      )
      (libsource (lib "28Pins") (part "RC0805FR-0710KL"))
    )
    (comp (ref "R22")
      (value "560R")
      (footprint "R0805")
      (description "Surface Mount Thick Film Resistor, RC Series, 560 ohm, 125 mW, - 1%, 150 V, 0805 [2012 Metric]")
      (fields
        (field (name "MANUFACTURER") "Yageo")
        (field (name "MANUFACTURER PART NUMBER") "RC0805FR-07560RL")
      )
      (libsource (lib "28Pins") (part "RC0805FR-07560RL"))
    )
    (comp (ref "R23")
      (value "22R")
      (footprint "R0805")
      (description "RES SMD 22 OHM 1% 1/8W 0805")
      (fields
        (field (name "MANUFACTURER") "Yageo")
        (field (name "MANUFACTURER PART NUMBER") "RC0805FR-0722RL")
      )
      (libsource (lib "28Pins") (part "RC0805FR-0722RL"))
    )
    (comp (ref "R24")
      (value "22R")
      (footprint "R0805")
      (description "RES SMD 22 OHM 1% 1/8W 0805")
      (fields
        (field (name "MANUFACTURER") "Yageo")
        (field (name "MANUFACTURER PART NUMBER") "RC0805FR-0722RL")
      )
      (libsource (lib "28Pins") (part "RC0805FR-0722RL"))
    )
    (comp (ref "R25")
      (value "22R")
      (footprint "R0805")
      (description "RES SMD 22 OHM 1% 1/8W 0805")
      (fields
        (field (name "MANUFACTURER") "Yageo")
        (field (name "MANUFACTURER PART NUMBER") "RC0805FR-0722RL")
      )
      (libsource (lib "28Pins") (part "RC0805FR-0722RL"))
    )
    (comp (ref "R26")
      (value "0R")
      (footprint "R0805")
      (description "Surface Mount Thick Film Resistor, RC Series, 125 mW, - 5%, 150 V, 0805 [2012 Metric]")
      (fields
        (field (name "MANUFACTURER") "Yageo")
        (field (name "MANUFACTURER PART NUMBER") "RC0805JR-070RL")
      )
      (libsource (lib "28Pins") (part "RC0805JR-070RL"))
    )
    (comp (ref "R27")
      (value "0R")
      (footprint "R0805")
      (description "Surface Mount Thick Film Resistor, RC Series, 125 mW, - 5%, 150 V, 0805 [2012 Metric]")
      (fields
        (field (name "MANUFACTURER") "Yageo")
        (field (name "MANUFACTURER PART NUMBER") "RC0805JR-070RL")
      )
      (libsource (lib "28Pins") (part "RC0805JR-070RL"))
    )
    (comp (ref "R28")
      (value "0R")
      (footprint "R0805")
      (description "Surface Mount Thick Film Resistor, RC Series, 125 mW, - 5%, 150 V, 0805 [2012 Metric]")
      (fields
        (field (name "MANUFACTURER") "Yageo")
        (field (name "MANUFACTURER PART NUMBER") "RC0805JR-070RL")
      )
      (libsource (lib "28Pins") (part "RC0805JR-070RL"))
    )
    (comp (ref "SCKT FOR U1")
      (value "28-DIP Socket")
      (footprint "28_DIP_7.62mm_SOCKET")
      (description "CONN IC DIP SOCKET 28POS TIN")
      (fields (field (name "MANUFACTURER") "3M") (field (name "MANUFACTURER PART NUMBER") "4828-3004-CP"))
      (libsource (lib "28Pins") (part "4828-3004-CP"))
    )
    (comp (ref "SW1")
      (value "1825910-6")
      (footprint "1825910-6")
      (description "SWITCH TACTILE SPST-NO 0.05A 24V")
      (fields (field (name "MANUFACTURER") "TE Connectivity Alcoswitch"))
      (libsource (lib "28Pins") (part "1825910-6"))
    )
    (comp (ref "SW2")
      (value "1825910-6")
      (footprint "1825910-6")
      (description "SWITCH TACTILE SPST-NO 0.05A 24V")
      (fields (field (name "MANUFACTURER") "TE Connectivity Alcoswitch"))
      (libsource (lib "28Pins") (part "1825910-6"))
    )
    (comp (ref "U1")
      (value "ATMEGA328P-PU")
      (footprint "28_DIP_7.62mm")
      (description "ATMEGA328P-PU; 8 bit Microcontroller AVR 20MHz 1; 32kb Flash; 2kb RAM; I2C SPI 2")
      (fields (field (name "MANUFACTURER") "Microchip / Atmel"))
      (libsource (lib "28Pins") (part "ATMEGA328P-PU"))
    )
    (comp (ref "U2")
      (value "ATMEGA16U2-AU")
      (footprint "TQFP32")
      (description "MICROCHIP - ATMEGA16U2-AU - MCU, 8BIT, MEGAAVR, 16MHZ, TQFP-32")
      (fields (field (name "MANUFACTURER") "Microchip / Atmel"))
      (libsource (lib "28Pins") (part "ATMEGA16U2-AU"))
    )
    (comp (ref "U3")
      (value "TL1963A-33DCQR")
      (footprint "DCQ (R-PDSO-G6)")
      (description "IC REG LINEAR 3.3V 1.5A SOT223-6")
      (fields (field (name "MANUFACTURER") "Texas Instruments"))
      (libsource (lib "28Pins") (part "TL1963A-33DCQR"))
    )
    (comp (ref "U4")
      (value "SN74AHC1G09DBVR")
      (footprint "DBV_SOT_23_5")
      (description "TEXAS INSTRUMENTS - SN74AHC1G09DBVR - AND Gate, 74AHC1G09, 2 Input, 2 V to 5.5 V, SOT-23-5")
      (fields (field (name "MANUFACTURER") "Texas Instruments"))
      (libsource (lib "28Pins") (part "SN74AHC1G09DBVR"))
    )
    (comp (ref "U5")
      (value "SN74AHC1G09DBVR")
      (footprint "DBV_SOT_23_5")
      (description "TEXAS INSTRUMENTS - SN74AHC1G09DBVR - AND Gate, 74AHC1G09, 2 Input, 2 V to 5.5 V, SOT-23-5")
      (fields (field (name "MANUFACTURER") "Texas Instruments"))
      (libsource (lib "28Pins") (part "SN74AHC1G09DBVR"))
    )
    (comp (ref "U6")
      (value "SN74AHC1G09DBVR")
      (footprint "DBV_SOT_23_5")
      (description "TEXAS INSTRUMENTS - SN74AHC1G09DBVR - AND Gate, 74AHC1G09, 2 Input, 2 V to 5.5 V, SOT-23-5")
      (fields (field (name "MANUFACTURER") "Texas Instruments"))
      (libsource (lib "28Pins") (part "SN74AHC1G09DBVR"))
    )
    (comp (ref "U7")
      (value "SN74AHC1G09DBVR")
      (footprint "DBV_SOT_23_5")
      (description "TEXAS INSTRUMENTS - SN74AHC1G09DBVR - AND Gate, 74AHC1G09, 2 Input, 2 V to 5.5 V, SOT-23-5")
      (fields (field (name "MANUFACTURER") "Texas Instruments"))
      (libsource (lib "28Pins") (part "SN74AHC1G09DBVR"))
    )
    (comp (ref "Y1")
      (value "ABM7-16.000MHZ-D2Y-T")
      (footprint "ABM7_v1_1_BIG")
      (description "CRYSTAL 16.0000MHZ 18PF SMD")
      (fields (field (name "MANUFACTURER") "Abracon") (field (name "TOLERANCE") "20ppm"))
      (libsource (lib "28Pins") (part "ABM7-16.000MHZ-D2Y-T"))
    )
    (comp (ref "Y2")
      (value "ABM7-16.000MHZ-D2Y-T")
      (footprint "ABM7_v1_1_BIG")
      (description "CRYSTAL 16.0000MHZ 18PF SMD")
      (fields (field (name "MANUFACTURER") "Abracon") (field (name "TOLERANCE") "20ppm"))
      (libsource (lib "28Pins") (part "ABM7-16.000MHZ-D2Y-T"))
    )
    (comp (ref "Z1")
      (value "CG0603MLC-05E")
      (footprint "R0603")
      (description "VARISTOR 0603")
      (fields (field (name "MANUFACTURER") "Bourns") (field (name "VOLTAGE") "5V"))
      (libsource (lib "28Pins") (part "CG0603MLC-05E"))
    )
    (comp (ref "Z2")
      (value "CG0603MLC-05E")
      (footprint "R0603")
      (description "VARISTOR 0603")
      (fields (field (name "MANUFACTURER") "Bourns") (field (name "VOLTAGE") "5V"))
      (libsource (lib "28Pins") (part "CG0603MLC-05E"))
    )
  )
  (nets
    (net (code "1") (name "+3.3V") (class "Default")
      (node (ref "C13") (pin "2") (pinfunction "2_2") (pintype "passive"))
      (node (ref "JP4") (pin "3") (pinfunction "3_3") (pintype "passive"))
      (node (ref "R28") (pin "2") (pinfunction "2_2") (pintype "passive"))
      (node (ref "U3") (pin "4") (pinfunction "OUT_4") (pintype "passive"))
      (node (ref "U3") (pin "5") (pinfunction "SENSE_5") (pintype "passive"))
    )
    (net (code "2") (name "+3V3") (class "Default")
      (node (ref "C16") (pin "2") (pinfunction "2_2") (pintype "passive"))
      (node (ref "J1") (pin "4") (pinfunction "4_4") (pintype "passive"))
    )
    (net (code "3") (name "+5V") (class "Default")
      (node (ref "C12") (pin "2") (pinfunction "2_2") (pintype "passive"))
      (node (ref "C14") (pin "2") (pinfunction "2_2") (pintype "passive"))
      (node (ref "C2") (pin "1") (pinfunction "1_1") (pintype "passive"))
      (node (ref "C6") (pin "2") (pinfunction "2_2") (pintype "passive"))
      (node (ref "J1") (pin "5") (pinfunction "5_5") (pintype "passive"))
      (node (ref "J8") (pin "1") (pinfunction "1_1") (pintype "passive"))
      (node (ref "JP4") (pin "1") (pinfunction "1_1") (pintype "passive"))
      (node (ref "L1") (pin "2") (pinfunction "2_2") (pintype "passive"))
      (node (ref "R27") (pin "1") (pinfunction "1_1") (pintype "passive"))
      (node (ref "U2") (pin "31") (pinfunction "UVCC_31") (pintype "passive"))
      (node (ref "U3") (pin "1") (pinfunction "~{SHD}N_1") (pintype "passive"))
      (node (ref "U3") (pin "2") (pinfunction "IN_2") (pintype "passive"))
    )
    (net (code "4") (name "+5V{slash}3V3") (class "Default")
      (node (ref "C15") (pin "2") (pinfunction "2_2") (pintype "passive"))
      (node (ref "C17") (pin "2") (pinfunction "2_2") (pintype "passive"))
      (node (ref "C26") (pin "2") (pinfunction "2_2") (pintype "passive"))
      (node (ref "C28") (pin "2") (pinfunction "2_2") (pintype "passive"))
      (node (ref "C29") (pin "2") (pinfunction "2_2") (pintype "passive"))
      (node (ref "C30") (pin "2") (pinfunction "2_2") (pintype "passive"))
      (node (ref "C34") (pin "2") (pinfunction "2_2") (pintype "passive"))
      (node (ref "C8") (pin "2") (pinfunction "2_2") (pintype "passive"))
      (node (ref "D5") (pin "1") (pinfunction "Cathode_1") (pintype "passive"))
      (node (ref "D6") (pin "1") (pinfunction "Cathode_1") (pintype "passive"))
      (node (ref "FB1") (pin "1") (pinfunction "1_1") (pintype "passive"))
      (node (ref "FB2") (pin "1") (pinfunction "1_1") (pintype "passive"))
      (node (ref "FB3") (pin "1") (pinfunction "1_1") (pintype "passive"))
      (node (ref "J1") (pin "2") (pinfunction "2_2") (pintype "passive"))
      (node (ref "J5") (pin "2") (pinfunction "2_2") (pintype "passive"))
      (node (ref "J6") (pin "2") (pinfunction "2_2") (pintype "passive"))
      (node (ref "JP4") (pin "2") (pinfunction "2_2") (pintype "passive"))
      (node (ref "R1") (pin "2") (pinfunction "2_2") (pintype "passive"))
      (node (ref "R14") (pin "2") (pinfunction "2_2") (pintype "passive"))
      (node (ref "R15") (pin "2") (pinfunction "2_2") (pintype "passive"))
      (node (ref "R17") (pin "2") (pinfunction "2_2") (pintype "passive"))
      (node (ref "R18") (pin "2") (pinfunction "2_2") (pintype "passive"))
      (node (ref "R19") (pin "2") (pinfunction "2_2") (pintype "passive"))
      (node (ref "R2") (pin "2") (pinfunction "2_2") (pintype "passive"))
      (node (ref "R20") (pin "2") (pinfunction "2_2") (pintype "passive"))
      (node (ref "R21") (pin "2") (pinfunction "2_2") (pintype "passive"))
      (node (ref "R27") (pin "2") (pinfunction "2_2") (pintype "passive"))
      (node (ref "R28") (pin "1") (pinfunction "1_1") (pintype "passive"))
      (node (ref "R3") (pin "2") (pinfunction "2_2") (pintype "passive"))
      (node (ref "R4") (pin "2") (pinfunction "2_2") (pintype "passive"))
      (node (ref "U4") (pin "5") (pinfunction "5_5") (pintype "passive"))
      (node (ref "U5") (pin "5") (pinfunction "5_5") (pintype "passive"))
      (node (ref "U6") (pin "5") (pinfunction "5_5") (pintype "passive"))
      (node (ref "U7") (pin "5") (pinfunction "5_5") (pintype "passive"))
    )
    (net (code "5") (name "+AREF") (class "Default")
      (node (ref "C21") (pin "1") (pinfunction "1_1") (pintype "passive"))
      (node (ref "C24") (pin "1") (pinfunction "1_1") (pintype "passive"))
      (node (ref "J4") (pin "8") (pinfunction "8_8") (pintype "passive"))
      (node (ref "U1") (pin "21") (pinfunction "AREF_21") (pintype "passive"))
    )
    (net (code "6") (name "/+5V_USB") (class "Default")
      (node (ref "C1") (pin "1") (pinfunction "1_1") (pintype "passive"))
      (node (ref "J7") (pin "1") (pinfunction "1_1") (pintype "passive"))
      (node (ref "L1") (pin "1") (pinfunction "1_1") (pintype "passive"))
    )
    (net (code "7") (name "/+5V{slash}3V3_16U2") (class "Default")
      (node (ref "C3") (pin "2") (pinfunction "2_2") (pintype "passive"))
      (node (ref "C4") (pin "2") (pinfunction "2_2") (pintype "passive"))
      (node (ref "C5") (pin "2") (pinfunction "2_2") (pintype "passive"))
      (node (ref "FB1") (pin "2") (pinfunction "2_2") (pintype "passive"))
      (node (ref "R26") (pin "2") (pinfunction "2_2") (pintype "passive"))
      (node (ref "U2") (pin "32") (pinfunction "AVCC_32") (pintype "passive"))
      (node (ref "U2") (pin "4") (pinfunction "VCC_4") (pintype "passive"))
    )
    (net (code "8") (name "/+5V{slash}3V3_328P_AVCC") (class "Default")
      (node (ref "C22") (pin "2") (pinfunction "2_2") (pintype "passive"))
      (node (ref "C23") (pin "2") (pinfunction "2_2") (pintype "passive"))
      (node (ref "FB3") (pin "2") (pinfunction "2_2") (pintype "passive"))
      (node (ref "U1") (pin "20") (pinfunction "AVCC_20") (pintype "passive"))
    )
    (net (code "9") (name "/+5V{slash}3V3_328P_VCC") (class "Default")
      (node (ref "C19") (pin "2") (pinfunction "2_2") (pintype "passive"))
      (node (ref "C20") (pin "2") (pinfunction "2_2") (pintype "passive"))
      (node (ref "FB2") (pin "2") (pinfunction "2_2") (pintype "passive"))
      (node (ref "U1") (pin "7") (pinfunction "VCC_7") (pintype "passive"))
    )
    (net (code "10") (name "/3V3_16U2_UCAP") (class "Default")
      (node (ref "C7") (pin "2") (pinfunction "2_2") (pintype "passive"))
      (node (ref "R26") (pin "1") (pinfunction "1_1") (pintype "passive"))
      (node (ref "U2") (pin "27") (pinfunction "UCAP_27") (pintype "passive"))
    )
    (net (code "11") (name "/16U2PROG_328P_RESETn") (class "Default")
      (node (ref "JP1") (pin "2") (pinfunction "2_2") (pintype "passive"))
      (node (ref "R1") (pin "1") (pinfunction "1_1") (pintype "passive"))
      (node (ref "U2") (pin "13") (pinfunction "~{CTS}_/_~{HWB}_/_T0_/_AIN6_/_INT7_/_PD7_13") (pintype "passive"))
    )
    (net (code "12") (name "/16U2_16MHZ_XTAL1") (class "Default")
      (node (ref "C10") (pin "2") (pinfunction "2_2") (pintype "passive"))
      (node (ref "R9") (pin "1") (pinfunction "1_1") (pintype "passive"))
      (node (ref "U2") (pin "1") (pinfunction "XTAL1_1") (pintype "passive"))
      (node (ref "Y2") (pin "1") (pinfunction "1_1") (pintype "passive"))
    )
    (net (code "13") (name "/16U2_16MHZ_XTAL2") (class "Default")
      (node (ref "C9") (pin "2") (pinfunction "2_2") (pintype "passive"))
      (node (ref "R9") (pin "2") (pinfunction "2_2") (pintype "passive"))
      (node (ref "U2") (pin "2") (pinfunction "XTAL2_/_PC0_2") (pintype "passive"))
      (node (ref "Y2") (pin "2") (pinfunction "2_2") (pintype "passive"))
    )
    (net (code "14") (name "/16U2_BUF_RESETn") (class "Default")
      (node (ref "C31") (pin "2") (pinfunction "2_2") (pintype "passive"))
      (node (ref "R23") (pin "2") (pinfunction "2_2") (pintype "passive"))
      (node (ref "U5") (pin "1") (pinfunction "1_1") (pintype "passive"))
      (node (ref "U5") (pin "2") (pinfunction "2_2") (pintype "passive"))
    )
    (net (code "15") (name "/16U2_HDR_RESETn") (class "Default")
      (node (ref "J6") (pin "5") (pinfunction "5_5") (pintype "passive"))
      (node (ref "JP3") (pin "3") (pinfunction "3_3") (pintype "passive"))
    )
    (net (code "16") (name "/16U2_MISO") (class "Default")
      (node (ref "J6") (pin "1") (pinfunction "1_1") (pintype "passive"))
      (node (ref "U2") (pin "17") (pinfunction "PDO_/_MISO_/_PCINT3_/_PB3_17") (pintype "passive"))
    )
    (net (code "17") (name "/16U2_MOSI") (class "Default")
      (node (ref "J6") (pin "4") (pinfunction "4_4") (pintype "passive"))
      (node (ref "U2") (pin "16") (pinfunction "PDI_/_MOSI_/_PCINT2_/_PB2_16") (pintype "passive"))
    )
    (net (code "18") (name "/16U2_PB4") (class "Default")
      (node (ref "JP2") (pin "1") (pinfunction "1_1") (pintype "passive"))
      (node (ref "JP3") (pin "2") (pinfunction "2_2") (pintype "passive"))
      (node (ref "U2") (pin "18") (pinfunction "T1_/_PCINT4_/_PB4_18") (pintype "passive"))
    )
    (net (code "19") (name "/16U2_PB5") (class "Default")
      (node (ref "JP2") (pin "3") (pinfunction "3_3") (pintype "passive"))
      (node (ref "U2") (pin "19") (pinfunction "PCINT5_/_PB5_19") (pintype "passive"))
    )
    (net (code "20") (name "/16U2_PB6") (class "Default")
      (node (ref "JP2") (pin "2") (pinfunction "2_2") (pintype "passive"))
      (node (ref "U2") (pin "20") (pinfunction "PCINT6_/_PB6_20") (pintype "passive"))
    )
    (net (code "21") (name "/16U2_PB7") (class "Default")
      (node (ref "JP2") (pin "4") (pinfunction "4_4") (pintype "passive"))
      (node (ref "U2") (pin "21") (pinfunction "OC.0A_/_OC.1C_/_PCINT7_/_PB7_21") (pintype "passive"))
    )
    (net (code "22") (name "/16U2_RESETn") (class "Default")
      (node (ref "JP3") (pin "4") (pinfunction "4_4") (pintype "passive"))
      (node (ref "R4") (pin "1") (pinfunction "1_1") (pintype "passive"))
      (node (ref "U2") (pin "24") (pinfunction "PC1_/_~{Reset}_/_dW_24") (pintype "passive"))
      (node (ref "U5") (pin "4") (pinfunction "4_4") (pintype "passive"))
    )
    (net (code "23") (name "/16U2_RXD") (class "Default")
      (node (ref "R11") (pin "1") (pinfunction "1_1") (pintype "passive"))
      (node (ref "U2") (pin "8") (pinfunction "RXD1_/_AIN1_/_INT2_/_PD2_8") (pintype "passive"))
    )
    (net (code "24") (name "/16U2_RX_LED") (class "Default")
      (node (ref "D4") (pin "1") (pinfunction "Cathode_1") (pintype "passive"))
      (node (ref "U2") (pin "10") (pinfunction "AIN3_/_INT5_/_PD4_10") (pintype "passive"))
    )
    (net (code "25") (name "/16U2_SCLK") (class "Default")
      (node (ref "J6") (pin "3") (pinfunction "3_3") (pintype "passive"))
      (node (ref "R5") (pin "2") (pinfunction "2_2") (pintype "passive"))
    )
    (net (code "26") (name "/16U2_SCLK_R") (class "Default")
      (node (ref "R5") (pin "1") (pinfunction "1_1") (pintype "passive"))
      (node (ref "U2") (pin "15") (pinfunction "SCLK_/_PCINT1_/_PB1_15") (pintype "passive"))
    )
    (net (code "27") (name "/16U2_TXD") (class "Default")
      (node (ref "R10") (pin "1") (pinfunction "1_1") (pintype "passive"))
      (node (ref "U2") (pin "9") (pinfunction "TXD1_/_INT3_/_PD3_9") (pintype "passive"))
    )
    (net (code "28") (name "/16U2_TX_LED") (class "Default")
      (node (ref "D3") (pin "1") (pinfunction "Cathode_1") (pintype "passive"))
      (node (ref "U2") (pin "11") (pinfunction "XCK_/_AIN4_/_PCINT12_/_PD5_11") (pintype "passive"))
    )
    (net (code "29") (name "/328P_16MHZ_XTAL1") (class "Default")
      (node (ref "C27") (pin "2") (pinfunction "2_2") (pintype "passive"))
      (node (ref "R16") (pin "1") (pinfunction "1_1") (pintype "passive"))
      (node (ref "U1") (pin "9") (pinfunction "PB6_(PCINT6/XTAL1/TOSC1)_9") (pintype "passive"))
      (node (ref "Y1") (pin "1") (pinfunction "1_1") (pintype "passive"))
    )
    (net (code "30") (name "/328P_16MHZ_XTAL2") (class "Default")
      (node (ref "C25") (pin "2") (pinfunction "2_2") (pintype "passive"))
      (node (ref "R16") (pin "2") (pinfunction "2_2") (pintype "passive"))
      (node (ref "U1") (pin "10") (pinfunction "PB7_(PCINT7/XTAL2/TOSC2)_10") (pintype "passive"))
      (node (ref "Y1") (pin "2") (pinfunction "2_2") (pintype "passive"))
    )
    (net (code "31") (name "/328P_AUTORESETn") (class "Default")
      (node (ref "C11") (pin "1") (pinfunction "1_1") (pintype "passive"))
      (node (ref "R18") (pin "1") (pinfunction "1_1") (pintype "passive"))
      (node (ref "U6") (pin "1") (pinfunction "1_1") (pintype "passive"))
    )
    (net (code "32") (name "/328P_BUF_RESETn") (class "Default")
      (node (ref "C32") (pin "2") (pinfunction "2_2") (pintype "passive"))
      (node (ref "R24") (pin "2") (pinfunction "2_2") (pintype "passive"))
      (node (ref "U6") (pin "2") (pinfunction "2_2") (pintype "passive"))
    )
    (net (code "33") (name "/328P_RESETn") (class "Default")
      (node (ref "J1") (pin "3") (pinfunction "3_3") (pintype "passive"))
      (node (ref "J5") (pin "5") (pinfunction "5_5") (pintype "passive"))
      (node (ref "JP3") (pin "1") (pinfunction "1_1") (pintype "passive"))
      (node (ref "R14") (pin "1") (pinfunction "1_1") (pintype "passive"))
      (node (ref "U1") (pin "1") (pinfunction "PC6_(PCINT14/_~{RESET})_1") (pintype "passive"))
      (node (ref "U6") (pin "4") (pinfunction "4_4") (pintype "passive"))
    )
    (net (code "34") (name "/AD0") (class "Default")
      (node (ref "J2") (pin "1") (pinfunction "1_1") (pintype "passive"))
      (node (ref "U1") (pin "23") (pinfunction "(ADC0/PCINT8)_PC0_23") (pintype "passive"))
    )
    (net (code "35") (name "/AD1") (class "Default")
      (node (ref "J2") (pin "2") (pinfunction "2_2") (pintype "passive"))
      (node (ref "U1") (pin "24") (pinfunction "(ADC1/PCINT9)_PC1_24") (pintype "passive"))
    )
    (net (code "36") (name "/AD2") (class "Default")
      (node (ref "J2") (pin "3") (pinfunction "3_3") (pintype "passive"))
      (node (ref "U1") (pin "25") (pinfunction "(ADC2/PCINT10)_PC2_25") (pintype "passive"))
    )
    (net (code "37") (name "/AD3") (class "Default")
      (node (ref "J2") (pin "4") (pinfunction "4_4") (pintype "passive"))
      (node (ref "U1") (pin "26") (pinfunction "(ADC3/PCINT11)_PC3_26") (pintype "passive"))
    )
    (net (code "38") (name "/AD4{slash}SDA") (class "Default")
      (node (ref "J2") (pin "5") (pinfunction "5_5") (pintype "passive"))
      (node (ref "J4") (pin "9") (pinfunction "9_9") (pintype "passive"))
      (node (ref "U1") (pin "27") (pinfunction "(ADC4/SDA/PCINT12)_PC4_27") (pintype "passive"))
    )
    (net (code "39") (name "/AD5{slash}SCL") (class "Default")
      (node (ref "J2") (pin "6") (pinfunction "6_6") (pintype "passive"))
      (node (ref "J4") (pin "10") (pinfunction "10_10") (pintype "passive"))
      (node (ref "U1") (pin "28") (pinfunction "(ADC5/SCL/PCINT13)_PC5_28") (pintype "passive"))
    )
    (net (code "40") (name "/BUTTON_RESETn") (class "Default")
      (node (ref "D6") (pin "2") (pinfunction "Anode_2") (pintype "passive"))
      (node (ref "R20") (pin "1") (pinfunction "1_1") (pintype "passive"))
      (node (ref "R24") (pin "1") (pinfunction "1_1") (pintype "passive"))
      (node (ref "SW1") (pin "1") (pinfunction "1_1") (pintype "passive"))
      (node (ref "SW1") (pin "2") (pinfunction "2_2") (pintype "passive"))
    )
    (net (code "41") (name "/CON_USB_N") (class "Default")
      (node (ref "J7") (pin "2") (pinfunction "2_2") (pintype "passive"))
      (node (ref "R6") (pin "1") (pinfunction "1_1") (pintype "passive"))
      (node (ref "Z1") (pin "2") (pinfunction "2_2") (pintype "passive"))
    )
    (net (code "42") (name "/CON_USB_P") (class "Default")
      (node (ref "J7") (pin "3") (pinfunction "3_3") (pintype "passive"))
      (node (ref "R7") (pin "1") (pinfunction "1_1") (pintype "passive"))
      (node (ref "Z2") (pin "2") (pinfunction "2_2") (pintype "passive"))
    )
    (net (code "43") (name "/IO0") (class "Default")
      (node (ref "J3") (pin "1") (pinfunction "1_1") (pintype "passive"))
      (node (ref "R10") (pin "2") (pinfunction "2_2") (pintype "passive"))
      (node (ref "U1") (pin "2") (pinfunction "(PCINT16/RXD)_PD0_2") (pintype "passive"))
    )
    (net (code "44") (name "/IO1") (class "Default")
      (node (ref "J3") (pin "2") (pinfunction "2_2") (pintype "passive"))
      (node (ref "R11") (pin "2") (pinfunction "2_2") (pintype "passive"))
      (node (ref "U1") (pin "3") (pinfunction "(PCINT17/TXD)_PD1_3") (pintype "passive"))
    )
    (net (code "45") (name "/IO2") (class "Default")
      (node (ref "J3") (pin "3") (pinfunction "3_3") (pintype "passive"))
      (node (ref "U1") (pin "4") (pinfunction "(PCINT18/INT0)_PD2_4") (pintype "passive"))
    )
    (net (code "46") (name "/IO3") (class "Default")
      (node (ref "J3") (pin "4") (pinfunction "4_4") (pintype "passive"))
      (node (ref "U1") (pin "5") (pinfunction "(PCINT19/OC2B/INT1)_PD3_5") (pintype "passive"))
    )
    (net (code "47") (name "/IO4") (class "Default")
      (node (ref "J3") (pin "5") (pinfunction "5_5") (pintype "passive"))
      (node (ref "U1") (pin "6") (pinfunction "(PCINT20/XCK/T0)_PD4_6") (pintype "passive"))
    )
    (net (code "48") (name "/IO5") (class "Default")
      (node (ref "J3") (pin "6") (pinfunction "6_6") (pintype "passive"))
      (node (ref "U1") (pin "11") (pinfunction "(PCINT21/OC0B/T1)_PD5_11") (pintype "passive"))
    )
    (net (code "49") (name "/IO6") (class "Default")
      (node (ref "J3") (pin "7") (pinfunction "7_7") (pintype "passive"))
      (node (ref "U1") (pin "12") (pinfunction "(PCINT22/OC0A/AIN0)_PD6_12") (pintype "passive"))
    )
    (net (code "50") (name "/IO7") (class "Default")
      (node (ref "J3") (pin "8") (pinfunction "8_8") (pintype "passive"))
      (node (ref "U1") (pin "13") (pinfunction "(PCINT23/AIN1)_PD7_13") (pintype "passive"))
    )
    (net (code "51") (name "/IO8") (class "Default")
      (node (ref "J4") (pin "1") (pinfunction "1_1") (pintype "passive"))
      (node (ref "R22") (pin "2") (pinfunction "2_2") (pintype "passive"))
      (node (ref "U1") (pin "14") (pinfunction "(PCINT0/CLKO/ICP1)_PB0_14") (pintype "passive"))
    )
    (net (code "52") (name "/IO9") (class "Default")
      (node (ref "J4") (pin "2") (pinfunction "2_2") (pintype "passive"))
      (node (ref "U1") (pin "15") (pinfunction "(OC1A/PCINT1)_PB1_15") (pintype "passive"))
    )
    (net (code "53") (name "/MISO") (class "Default")
      (node (ref "J4") (pin "5") (pinfunction "5_5") (pintype "passive"))
      (node (ref "J5") (pin "1") (pinfunction "1_1") (pintype "passive"))
      (node (ref "U1") (pin "18") (pinfunction "(MISO/PCINT4)_PB4_18") (pintype "passive"))
    )
    (net (code "54") (name "/MOSI") (class "Default")
      (node (ref "J4") (pin "4") (pinfunction "4_4") (pintype "passive"))
      (node (ref "J5") (pin "4") (pinfunction "4_4") (pintype "passive"))
      (node (ref "U1") (pin "17") (pinfunction "(MOSI/OC2A/PCINT3)_PB3_17") (pintype "passive"))
    )
    (net (code "55") (name "/SCK") (class "Default")
      (node (ref "J4") (pin "6") (pinfunction "6_6") (pintype "passive"))
      (node (ref "J5") (pin "3") (pinfunction "3_3") (pintype "passive"))
      (node (ref "R13") (pin "2") (pinfunction "2_2") (pintype "passive"))
      (node (ref "U4") (pin "1") (pinfunction "1_1") (pintype "passive"))
      (node (ref "U4") (pin "2") (pinfunction "2_2") (pintype "passive"))
    )
    (net (code "56") (name "/SCK_R") (class "Default")
      (node (ref "R13") (pin "1") (pinfunction "1_1") (pintype "passive"))
      (node (ref "U1") (pin "19") (pinfunction "(SCK/PCINT5)_PB5_19") (pintype "passive"))
    )
    (net (code "57") (name "/SS") (class "Default")
      (node (ref "J4") (pin "3") (pinfunction "3_3") (pintype "passive"))
      (node (ref "U1") (pin "16") (pinfunction "(SS/OC1B/PCINT2)_PB2_16") (pintype "passive"))
    )
    (net (code "58") (name "/USB_N") (class "Default")
      (node (ref "R6") (pin "2") (pinfunction "2_2") (pintype "passive"))
      (node (ref "U2") (pin "30") (pinfunction "D-_30") (pintype "passive"))
    )
    (net (code "59") (name "/USB_P") (class "Default")
      (node (ref "R7") (pin "2") (pinfunction "2_2") (pintype "passive"))
      (node (ref "U2") (pin "29") (pinfunction "D+_29") (pintype "passive"))
    )
    (net (code "60") (name "/USER_BUTTON") (class "Default")
      (node (ref "R21") (pin "1") (pinfunction "1_1") (pintype "passive"))
      (node (ref "R25") (pin "1") (pinfunction "1_1") (pintype "passive"))
      (node (ref "SW2") (pin "1") (pinfunction "1_1") (pintype "passive"))
      (node (ref "SW2") (pin "2") (pinfunction "2_2") (pintype "passive"))
    )
    (net (code "61") (name "/USER_BUTTON_BUF") (class "Default")
      (node (ref "C33") (pin "2") (pinfunction "2_2") (pintype "passive"))
      (node (ref "R25") (pin "2") (pinfunction "2_2") (pintype "passive"))
      (node (ref "U7") (pin "1") (pinfunction "1_1") (pintype "passive"))
      (node (ref "U7") (pin "2") (pinfunction "2_2") (pintype "passive"))
    )
    (net (code "62") (name "GND") (class "Default")
      (node (ref "C1") (pin "2") (pinfunction "2_2") (pintype "passive"))
      (node (ref "C10") (pin "1") (pinfunction "1_1") (pintype "passive"))
      (node (ref "C12") (pin "1") (pinfunction "1_1") (pintype "passive"))
      (node (ref "C13") (pin "1") (pinfunction "1_1") (pintype "passive"))
      (node (ref "C14") (pin "1") (pinfunction "1_1") (pintype "passive"))
      (node (ref "C15") (pin "1") (pinfunction "1_1") (pintype "passive"))
      (node (ref "C16") (pin "1") (pinfunction "1_1") (pintype "passive"))
      (node (ref "C17") (pin "1") (pinfunction "1_1") (pintype "passive"))
      (node (ref "C19") (pin "1") (pinfunction "1_1") (pintype "passive"))
      (node (ref "C2") (pin "2") (pinfunction "2_2") (pintype "passive"))
      (node (ref "C20") (pin "1") (pinfunction "1_1") (pintype "passive"))
      (node (ref "C21") (pin "2") (pinfunction "2_2") (pintype "passive"))
      (node (ref "C22") (pin "1") (pinfunction "1_1") (pintype "passive"))
      (node (ref "C23") (pin "1") (pinfunction "1_1") (pintype "passive"))
      (node (ref "C24") (pin "2") (pinfunction "2_2") (pintype "passive"))
      (node (ref "C25") (pin "1") (pinfunction "1_1") (pintype "passive"))
      (node (ref "C26") (pin "1") (pinfunction "1_1") (pintype "passive"))
      (node (ref "C27") (pin "1") (pinfunction "1_1") (pintype "passive"))
      (node (ref "C28") (pin "1") (pinfunction "1_1") (pintype "passive"))
      (node (ref "C29") (pin "1") (pinfunction "1_1") (pintype "passive"))
      (node (ref "C3") (pin "1") (pinfunction "1_1") (pintype "passive"))
      (node (ref "C30") (pin "1") (pinfunction "1_1") (pintype "passive"))
      (node (ref "C31") (pin "1") (pinfunction "1_1") (pintype "passive"))
      (node (ref "C32") (pin "1") (pinfunction "1_1") (pintype "passive"))
      (node (ref "C33") (pin "1") (pinfunction "1_1") (pintype "passive"))
      (node (ref "C34") (pin "1") (pinfunction "1_1") (pintype "passive"))
      (node (ref "C4") (pin "1") (pinfunction "1_1") (pintype "passive"))
      (node (ref "C5") (pin "1") (pinfunction "1_1") (pintype "passive"))
      (node (ref "C6") (pin "1") (pinfunction "1_1") (pintype "passive"))
      (node (ref "C7") (pin "1") (pinfunction "1_1") (pintype "passive"))
      (node (ref "C8") (pin "1") (pinfunction "1_1") (pintype "passive"))
      (node (ref "C9") (pin "1") (pinfunction "1_1") (pintype "passive"))
      (node (ref "D1") (pin "1") (pinfunction "Cathode_1") (pintype "passive"))
      (node (ref "J1") (pin "6") (pinfunction "6_6") (pintype "passive"))
      (node (ref "J1") (pin "7") (pinfunction "7_7") (pintype "passive"))
      (node (ref "J4") (pin "7") (pinfunction "7_7") (pintype "passive"))
      (node (ref "J5") (pin "6") (pinfunction "6_6") (pintype "passive"))
      (node (ref "J6") (pin "6") (pinfunction "6_6") (pintype "passive"))
      (node (ref "J7") (pin "10") (pinfunction "10_10") (pintype "passive"))
      (node (ref "J7") (pin "11") (pinfunction "11_11") (pintype "passive"))
      (node (ref "J7") (pin "5") (pinfunction "5_5") (pintype "passive"))
      (node (ref "J7") (pin "6") (pinfunction "6_6") (pintype "passive"))
      (node (ref "J7") (pin "7") (pinfunction "7_7") (pintype "passive"))
      (node (ref "J7") (pin "8") (pinfunction "8_8") (pintype "passive"))
      (node (ref "J7") (pin "9") (pinfunction "9_9") (pintype "passive"))
      (node (ref "J9") (pin "1") (pinfunction "1_1") (pintype "passive"))
      (node (ref "MH1") (pin "1") (pinfunction "1_1") (pintype "passive"))
      (node (ref "MH2") (pin "1") (pinfunction "1_1") (pintype "passive"))
      (node (ref "MH3") (pin "1") (pinfunction "1_1") (pintype "passive"))
      (node (ref "R12") (pin "1") (pinfunction "1_1") (pintype "passive"))
      (node (ref "R8") (pin "2") (pinfunction "2_2") (pintype "passive"))
      (node (ref "SW1") (pin "3") (pinfunction "3_3") (pintype "passive"))
      (node (ref "SW1") (pin "4") (pinfunction "4_4") (pintype "passive"))
      (node (ref "SW2") (pin "3") (pinfunction "3_3") (pintype "passive"))
      (node (ref "SW2") (pin "4") (pinfunction "4_4") (pintype "passive"))
      (node (ref "U1") (pin "22") (pinfunction "GND_2_22") (pintype "passive"))
      (node (ref "U1") (pin "8") (pinfunction "GND_1_8") (pintype "passive"))
      (node (ref "U2") (pin "28") (pinfunction "UGND_28") (pintype "passive"))
      (node (ref "U2") (pin "3") (pinfunction "GND_3") (pintype "passive"))
      (node (ref "U3") (pin "3") (pinfunction "GND_3") (pintype "passive"))
      (node (ref "U3") (pin "6") (pinfunction "EPAD_6") (pintype "passive"))
      (node (ref "U4") (pin "3") (pinfunction "3_3") (pintype "passive"))
      (node (ref "U5") (pin "3") (pinfunction "3_3") (pintype "passive"))
      (node (ref "U6") (pin "3") (pinfunction "3_3") (pintype "passive"))
      (node (ref "U7") (pin "3") (pinfunction "3_3") (pintype "passive"))
      (node (ref "Z1") (pin "1") (pinfunction "1_1") (pintype "passive"))
      (node (ref "Z2") (pin "1") (pinfunction "1_1") (pintype "passive"))
    )
    (net (code "63") (name "Net-(C11-Pad2)") (class "Default")
      (node (ref "C11") (pin "2") (pinfunction "2_2") (pintype "passive"))
      (node (ref "JP1") (pin "1") (pinfunction "1_1") (pintype "passive"))
    )
    (net (code "64") (name "Net-(D1-Anode)") (class "Default")
      (node (ref "D1") (pin "2") (pinfunction "Anode_2") (pintype "passive"))
      (node (ref "R17") (pin "1") (pinfunction "1_1") (pintype "passive"))
    )
    (net (code "65") (name "Net-(D2-Anode)") (class "Default")
      (node (ref "D2") (pin "2") (pinfunction "Anode_2") (pintype "passive"))
      (node (ref "R15") (pin "1") (pinfunction "1_1") (pintype "passive"))
    )
    (net (code "66") (name "Net-(D2-Cathode)") (class "Default")
      (node (ref "D2") (pin "1") (pinfunction "Cathode_1") (pintype "passive"))
      (node (ref "U4") (pin "4") (pinfunction "4_4") (pintype "passive"))
    )
    (net (code "67") (name "Net-(D3-Anode)") (class "Default")
      (node (ref "D3") (pin "2") (pinfunction "Anode_2") (pintype "passive"))
      (node (ref "R2") (pin "1") (pinfunction "1_1") (pintype "passive"))
    )
    (net (code "68") (name "Net-(D4-Anode)") (class "Default")
      (node (ref "D4") (pin "2") (pinfunction "Anode_2") (pintype "passive"))
      (node (ref "R3") (pin "1") (pinfunction "1_1") (pintype "passive"))
    )
    (net (code "69") (name "Net-(D5-Anode)") (class "Default")
      (node (ref "D5") (pin "2") (pinfunction "Anode_2") (pintype "passive"))
      (node (ref "R19") (pin "1") (pinfunction "1_1") (pintype "passive"))
      (node (ref "R23") (pin "1") (pinfunction "1_1") (pintype "passive"))
    )
    (net (code "70") (name "Net-(J7-Pad4)") (class "Default")
      (node (ref "J7") (pin "4") (pinfunction "4_4") (pintype "passive"))
      (node (ref "R8") (pin "1") (pinfunction "1_1") (pintype "passive"))
    )
    (net (code "71") (name "Net-(JP1-Pad3)") (class "Default")
      (node (ref "JP1") (pin "3") (pinfunction "3_3") (pintype "passive"))
      (node (ref "R12") (pin "2") (pinfunction "2_2") (pintype "passive"))
    )
    (net (code "72") (name "Net-(R22-Pad1)") (class "Default")
      (node (ref "R22") (pin "1") (pinfunction "1_1") (pintype "passive"))
      (node (ref "U7") (pin "4") (pinfunction "4_4") (pintype "passive"))
    )
    (net (code "73") (name "unconnected-(J1-Pad1)") (class "Default")
      (node (ref "J1") (pin "1") (pinfunction "1_1") (pintype "passive+no_connect"))
    )
    (net (code "74") (name "unconnected-(J1-Pad8)") (class "Default")
      (node (ref "J1") (pin "8") (pinfunction "8_8") (pintype "passive+no_connect"))
    )
    (net (code "75") (name "unconnected-(MH4-Pad1)") (class "Default")
      (node (ref "MH4") (pin "1") (pinfunction "1_1") (pintype "passive+no_connect"))
    )
    (net (code "76") (name "unconnected-(U2-AIN0_{slash}_INT1_{slash}_PD1-Pad7)") (class "Default")
      (node (ref "U2") (pin "7") (pinfunction "AIN0_/_INT1_/_PD1_7") (pintype "passive+no_connect"))
    )
    (net (code "77") (name "unconnected-(U2-AIN2_{slash}_PCINT11_{slash}_PC2-Pad5)") (class "Default")
      (node (ref "U2") (pin "5") (pinfunction "AIN2_/_PCINT11_/_PC2_5") (pintype "passive+no_connect"))
    )
    (net (code "78") (name "unconnected-(U2-CLKO__{slash}_ICP1_{slash}_INT4_{slash}_PC7-Pad22)") (class "Default")
      (node (ref "U2") (pin "22") (pinfunction "CLKO__/_ICP1_/_INT4_/_PC7_22") (pintype "passive+no_connect"))
    )
    (net (code "79") (name "unconnected-(U2-OC.0B_{slash}_INT0_{slash}_PD0-Pad6)") (class "Default")
      (node (ref "U2") (pin "6") (pinfunction "OC.0B_/_INT0_/_PD0_6") (pintype "passive+no_connect"))
    )
    (net (code "80") (name "unconnected-(U2-OC.1A_{slash}_PCINT8_{slash}_PC6-Pad23)") (class "Default")
      (node (ref "U2") (pin "23") (pinfunction "OC.1A_/_PCINT8_/_PC6_23") (pintype "passive+no_connect"))
    )
    (net (code "81") (name "unconnected-(U2-OC.1B_{slash}_PCINT9_{slash}_PC5-Pad25)") (class "Default")
      (node (ref "U2") (pin "25") (pinfunction "OC.1B_/_PCINT9_/_PC5_25") (pintype "passive+no_connect"))
    )
    (net (code "82") (name "unconnected-(U2-PCINT10_{slash}_PC4-Pad26)") (class "Default")
      (node (ref "U2") (pin "26") (pinfunction "PCINT10_/_PC4_26") (pintype "passive+no_connect"))
    )
    (net (code "83") (name "unconnected-(U2-~{RTS}_{slash}_AIN5_{slash}_INT6_{slash}_PD6-Pad12)") (class "Default")
      (node (ref "U2") (pin "12") (pinfunction "~{RTS}_/_AIN5_/_INT6_/_PD6_12") (pintype "passive"))
    )
    (net (code "84") (name "unconnected-(U2-~{SS}_{slash}_PCINT0_{slash}_PB0-Pad14)") (class "Default")
      (node (ref "U2") (pin "14") (pinfunction "~{SS}_/_PCINT0_/_PB0_14") (pintype "passive+no_connect"))
    )
  )
)
